# SupplyBox_v3.net
KiCad netlist of a schematic drawn in Altium Designer
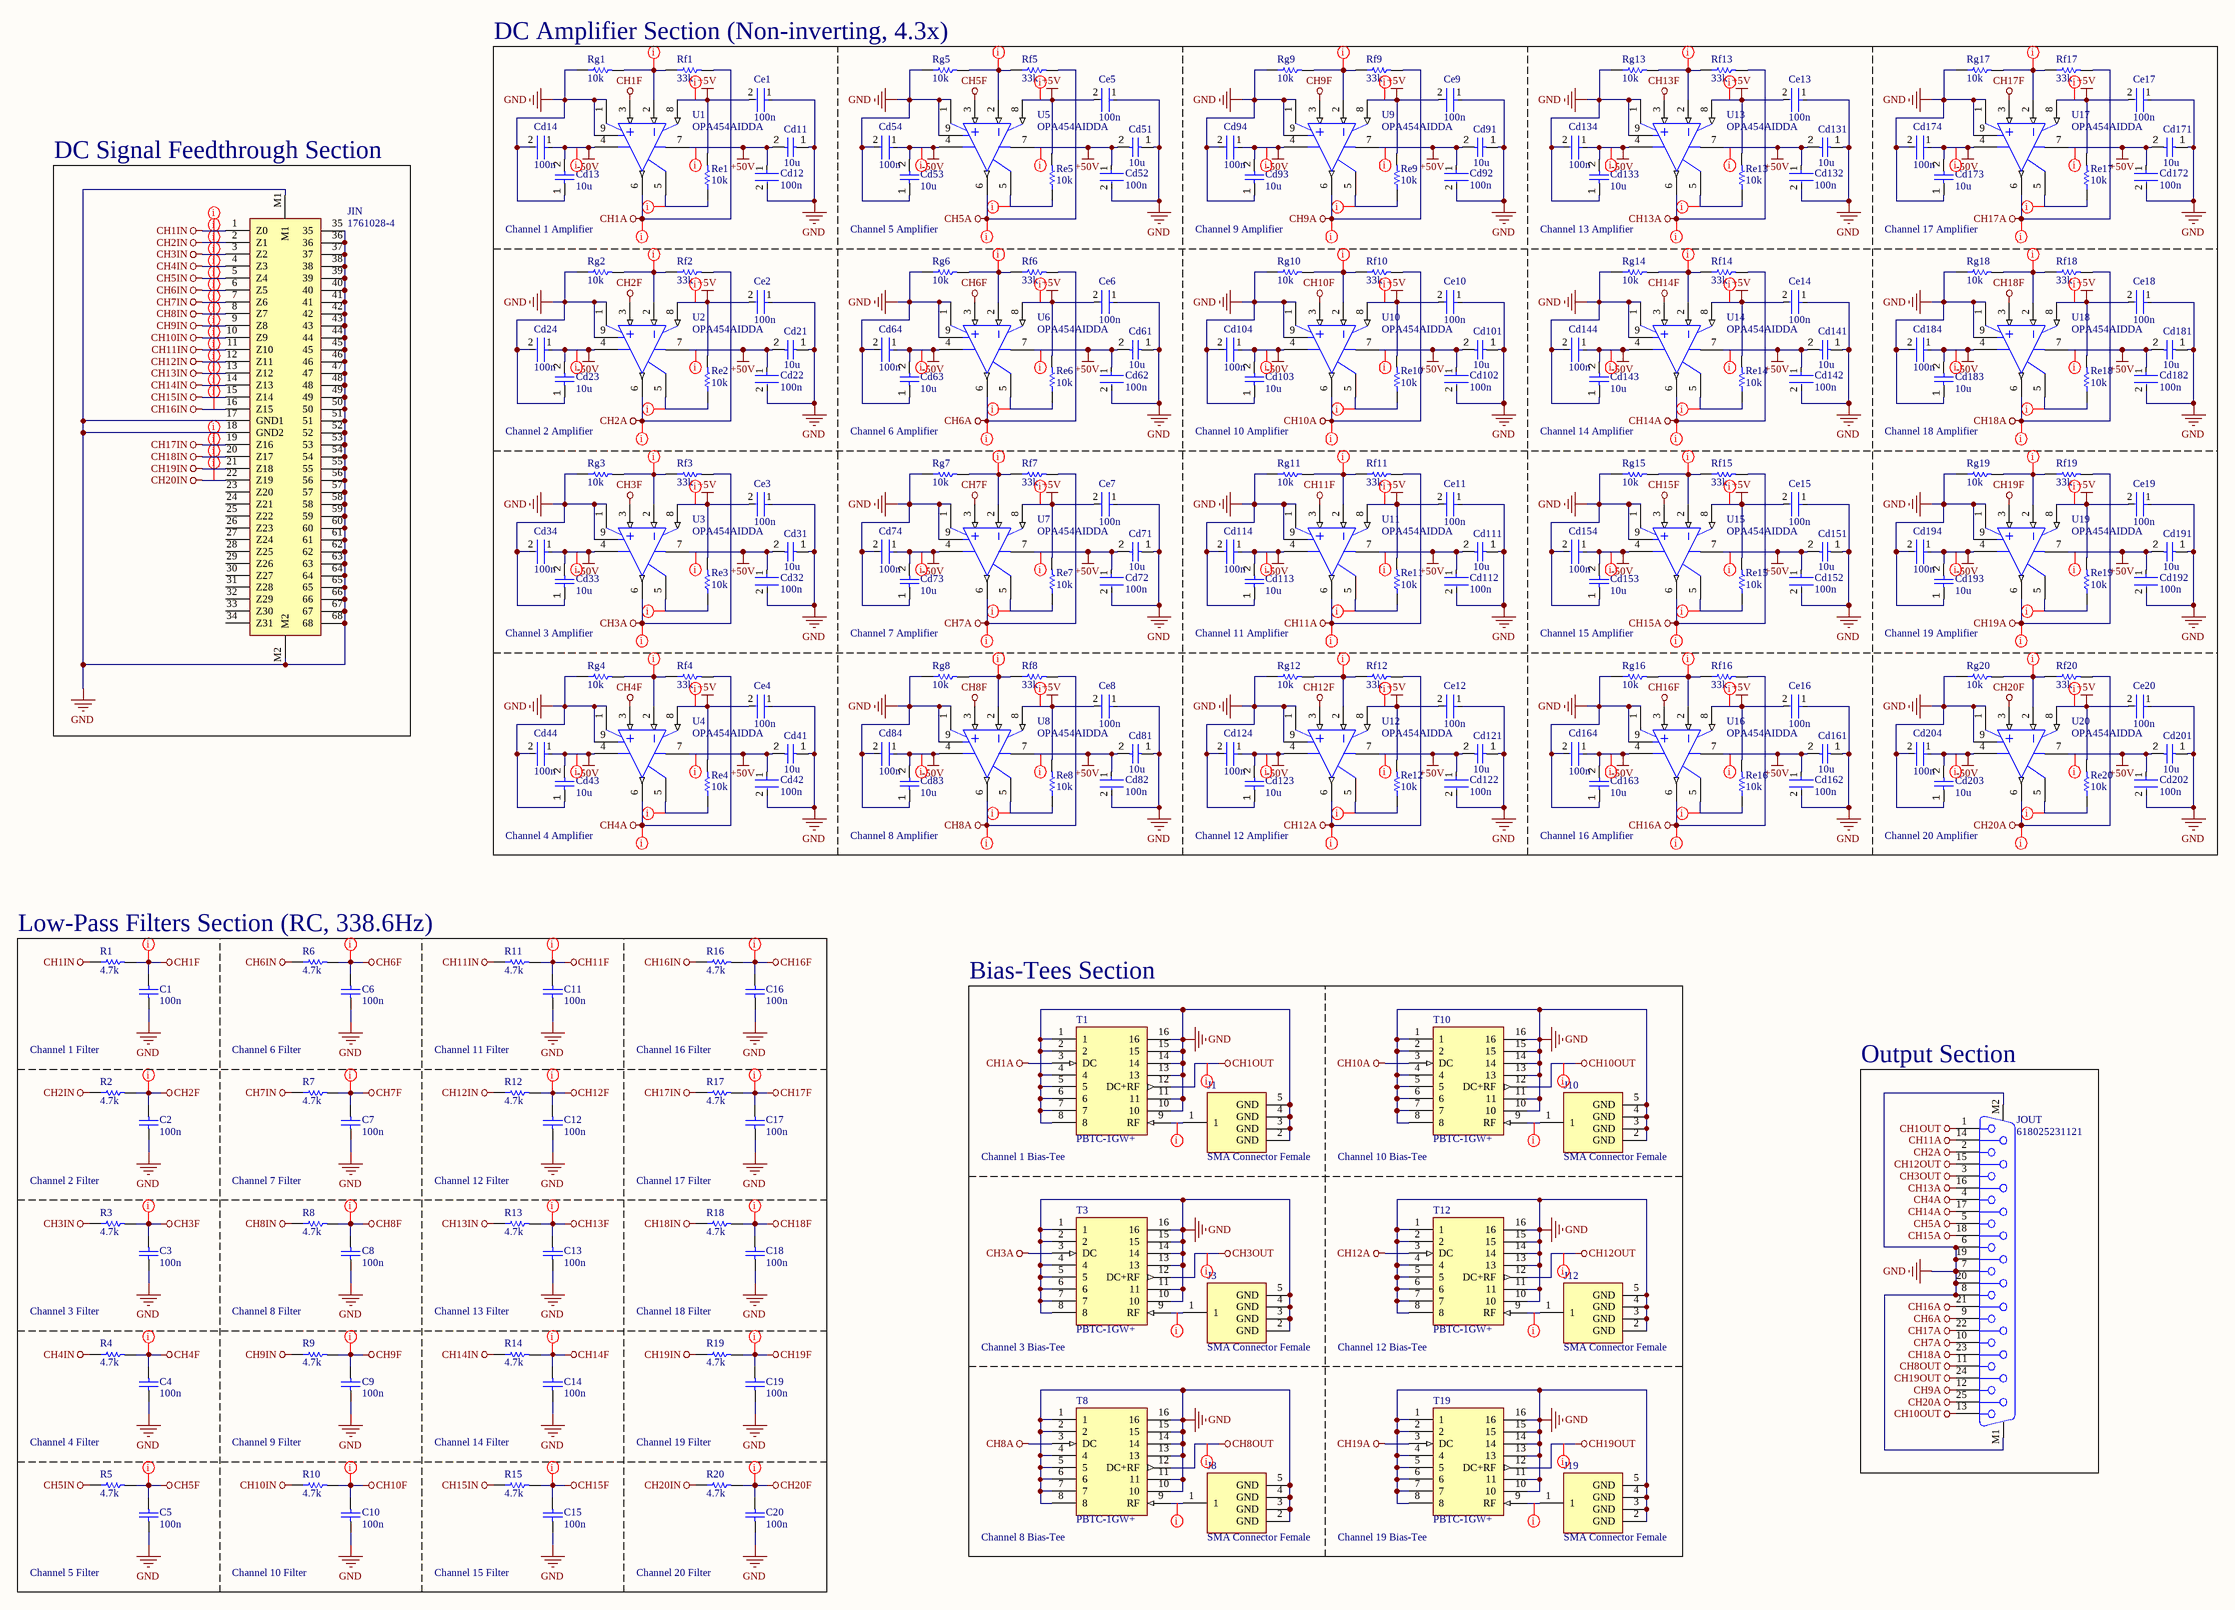
[diagram p0: SupplyBox_v3.SchDoc]

(export (version "E")
  (design (tool "Eeschema 10.0.6"))
  (components
    (comp (ref "C1")
      (value "100n")
      (footprint "CAPC2013X145X48NL20T23")
      (fields (field (name "MANUFACTURER") "Vitramon") (field (name "PART NUMBER") "VJ0805Y104KNAAT"))
      (libsource (lib "Altium Content Vault") (part "CAP"))
    )
    (comp (ref "C2")
      (value "100n")
      (footprint "CAPC2013X145X48NL20T23")
      (fields (field (name "MANUFACTURER") "Vitramon") (field (name "PART NUMBER") "VJ0805Y104KNAAT"))
      (libsource (lib "Altium Content Vault") (part "CAP"))
    )
    (comp (ref "C3")
      (value "100n")
      (footprint "CAPC2013X145X48NL20T23")
      (fields (field (name "MANUFACTURER") "Vitramon") (field (name "PART NUMBER") "VJ0805Y104KNAAT"))
      (libsource (lib "Altium Content Vault") (part "CAP"))
    )
    (comp (ref "C4")
      (value "100n")
      (footprint "CAPC2013X145X48NL20T23")
      (fields (field (name "MANUFACTURER") "Vitramon") (field (name "PART NUMBER") "VJ0805Y104KNAAT"))
      (libsource (lib "Altium Content Vault") (part "CAP"))
    )
    (comp (ref "C5")
      (value "100n")
      (footprint "CAPC2013X145X48NL20T23")
      (fields (field (name "MANUFACTURER") "Vitramon") (field (name "PART NUMBER") "VJ0805Y104KNAAT"))
      (libsource (lib "Altium Content Vault") (part "CAP"))
    )
    (comp (ref "C6")
      (value "100n")
      (footprint "CAPC2013X145X48NL20T23")
      (fields (field (name "MANUFACTURER") "Vitramon") (field (name "PART NUMBER") "VJ0805Y104KNAAT"))
      (libsource (lib "Altium Content Vault") (part "CAP"))
    )
    (comp (ref "C7")
      (value "100n")
      (footprint "CAPC2013X145X48NL20T23")
      (fields (field (name "MANUFACTURER") "Vitramon") (field (name "PART NUMBER") "VJ0805Y104KNAAT"))
      (libsource (lib "Altium Content Vault") (part "CAP"))
    )
    (comp (ref "C8")
      (value "100n")
      (footprint "CAPC2013X145X48NL20T23")
      (fields (field (name "MANUFACTURER") "Vitramon") (field (name "PART NUMBER") "VJ0805Y104KNAAT"))
      (libsource (lib "Altium Content Vault") (part "CAP"))
    )
    (comp (ref "C9")
      (value "100n")
      (footprint "CAPC2013X145X48NL20T23")
      (fields (field (name "MANUFACTURER") "Vitramon") (field (name "PART NUMBER") "VJ0805Y104KNAAT"))
      (libsource (lib "Altium Content Vault") (part "CAP"))
    )
    (comp (ref "C10")
      (value "100n")
      (footprint "CAPC2013X145X48NL20T23")
      (fields (field (name "MANUFACTURER") "Vitramon") (field (name "PART NUMBER") "VJ0805Y104KNAAT"))
      (libsource (lib "Altium Content Vault") (part "CAP"))
    )
    (comp (ref "C11")
      (value "100n")
      (footprint "CAPC2013X145X48NL20T23")
      (fields (field (name "MANUFACTURER") "Vitramon") (field (name "PART NUMBER") "VJ0805Y104KNAAT"))
      (libsource (lib "Altium Content Vault") (part "CAP"))
    )
    (comp (ref "C12")
      (value "100n")
      (footprint "CAPC2013X145X48NL20T23")
      (fields (field (name "MANUFACTURER") "Vitramon") (field (name "PART NUMBER") "VJ0805Y104KNAAT"))
      (libsource (lib "Altium Content Vault") (part "CAP"))
    )
    (comp (ref "C13")
      (value "100n")
      (footprint "CAPC2013X145X48NL20T23")
      (fields (field (name "MANUFACTURER") "Vitramon") (field (name "PART NUMBER") "VJ0805Y104KNAAT"))
      (libsource (lib "Altium Content Vault") (part "CAP"))
    )
    (comp (ref "C14")
      (value "100n")
      (footprint "CAPC2013X145X48NL20T23")
      (fields (field (name "MANUFACTURER") "Vitramon") (field (name "PART NUMBER") "VJ0805Y104KNAAT"))
      (libsource (lib "Altium Content Vault") (part "CAP"))
    )
    (comp (ref "C15")
      (value "100n")
      (footprint "CAPC2013X145X48NL20T23")
      (fields (field (name "MANUFACTURER") "Vitramon") (field (name "PART NUMBER") "VJ0805Y104KNAAT"))
      (libsource (lib "Altium Content Vault") (part "CAP"))
    )
    (comp (ref "C16")
      (value "100n")
      (footprint "CAPC2013X145X48NL20T23")
      (fields (field (name "MANUFACTURER") "Vitramon") (field (name "PART NUMBER") "VJ0805Y104KNAAT"))
      (libsource (lib "Altium Content Vault") (part "CAP"))
    )
    (comp (ref "C17")
      (value "100n")
      (footprint "CAPC2013X145X48NL20T23")
      (fields (field (name "MANUFACTURER") "Vitramon") (field (name "PART NUMBER") "VJ0805Y104KNAAT"))
      (libsource (lib "Altium Content Vault") (part "CAP"))
    )
    (comp (ref "C18")
      (value "100n")
      (footprint "CAPC2013X145X48NL20T23")
      (fields (field (name "MANUFACTURER") "Vitramon") (field (name "PART NUMBER") "VJ0805Y104KNAAT"))
      (libsource (lib "Altium Content Vault") (part "CAP"))
    )
    (comp (ref "C19")
      (value "100n")
      (footprint "CAPC2013X145X48NL20T23")
      (fields (field (name "MANUFACTURER") "Vitramon") (field (name "PART NUMBER") "VJ0805Y104KNAAT"))
      (libsource (lib "Altium Content Vault") (part "CAP"))
    )
    (comp (ref "C20")
      (value "100n")
      (footprint "CAPC2013X145X48NL20T23")
      (fields (field (name "MANUFACTURER") "Vitramon") (field (name "PART NUMBER") "VJ0805Y104KNAAT"))
      (libsource (lib "Altium Content Vault") (part "CAP"))
    )
    (comp (ref "Cd11")
      (value "10u")
      (footprint "RAHV1100M1UCC8002E-Footprint-1")
      (libsource (lib "Li-Ren Liu") (part "CAP-NP-2"))
    )
    (comp (ref "Cd12")
      (value "100n")
      (footprint "FP-CC0805-0_85-MFG")
      (description "CAP CER 0.1UF 25V X7R 0805")
      (fields (field (name "MANUFACTURER PART NUMBER") "CC0805KRX7R8BB104") (field (name "TOLERANCE") "0.1"))
      (libsource (lib "Altium Content Vault") (part "11868f565c42a9108669ba33697ecf6"))
    )
    (comp (ref "Cd13")
      (value "10u")
      (footprint "RAHV1100M1UCC8002E-Footprint-1")
      (libsource (lib "Li-Ren Liu") (part "CAP-NP-2"))
    )
    (comp (ref "Cd14")
      (value "100n")
      (footprint "FP-CC0805-0_85-MFG")
      (description "CAP CER 0.1UF 25V X7R 0805")
      (fields (field (name "MANUFACTURER PART NUMBER") "CC0805KRX7R8BB104") (field (name "TOLERANCE") "0.1"))
      (libsource (lib "Altium Content Vault") (part "11868f565c42a9108669ba33697ecf6"))
    )
    (comp (ref "Cd21")
      (value "10u")
      (footprint "RAHV1100M1UCC8002E-Footprint-1")
      (libsource (lib "Li-Ren Liu") (part "CAP-NP-2"))
    )
    (comp (ref "Cd22")
      (value "100n")
      (footprint "FP-CC0805-0_85-MFG")
      (description "CAP CER 0.1UF 25V X7R 0805")
      (fields (field (name "MANUFACTURER PART NUMBER") "CC0805KRX7R8BB104") (field (name "TOLERANCE") "0.1"))
      (libsource (lib "Altium Content Vault") (part "11868f565c42a9108669ba33697ecf6"))
    )
    (comp (ref "Cd23")
      (value "10u")
      (footprint "RAHV1100M1UCC8002E-Footprint-1")
      (libsource (lib "Li-Ren Liu") (part "CAP-NP-2"))
    )
    (comp (ref "Cd24")
      (value "100n")
      (footprint "FP-CC0805-0_85-MFG")
      (description "CAP CER 0.1UF 25V X7R 0805")
      (fields (field (name "MANUFACTURER PART NUMBER") "CC0805KRX7R8BB104") (field (name "TOLERANCE") "0.1"))
      (libsource (lib "Altium Content Vault") (part "11868f565c42a9108669ba33697ecf6"))
    )
    (comp (ref "Cd31")
      (value "10u")
      (footprint "RAHV1100M1UCC8002E-Footprint-1")
      (libsource (lib "Li-Ren Liu") (part "CAP-NP-2"))
    )
    (comp (ref "Cd32")
      (value "100n")
      (footprint "FP-CC0805-0_85-MFG")
      (description "CAP CER 0.1UF 25V X7R 0805")
      (fields (field (name "MANUFACTURER PART NUMBER") "CC0805KRX7R8BB104") (field (name "TOLERANCE") "0.1"))
      (libsource (lib "Altium Content Vault") (part "11868f565c42a9108669ba33697ecf6"))
    )
    (comp (ref "Cd33")
      (value "10u")
      (footprint "RAHV1100M1UCC8002E-Footprint-1")
      (libsource (lib "Li-Ren Liu") (part "CAP-NP-2"))
    )
    (comp (ref "Cd34")
      (value "100n")
      (footprint "FP-CC0805-0_85-MFG")
      (description "CAP CER 0.1UF 25V X7R 0805")
      (fields (field (name "MANUFACTURER PART NUMBER") "CC0805KRX7R8BB104") (field (name "TOLERANCE") "0.1"))
      (libsource (lib "Altium Content Vault") (part "11868f565c42a9108669ba33697ecf6"))
    )
    (comp (ref "Cd41")
      (value "10u")
      (footprint "RAHV1100M1UCC8002E-Footprint-1")
      (libsource (lib "Li-Ren Liu") (part "CAP-NP-2"))
    )
    (comp (ref "Cd42")
      (value "100n")
      (footprint "FP-CC0805-0_85-MFG")
      (description "CAP CER 0.1UF 25V X7R 0805")
      (fields (field (name "MANUFACTURER PART NUMBER") "CC0805KRX7R8BB104") (field (name "TOLERANCE") "0.1"))
      (libsource (lib "Altium Content Vault") (part "11868f565c42a9108669ba33697ecf6"))
    )
    (comp (ref "Cd43")
      (value "10u")
      (footprint "RAHV1100M1UCC8002E-Footprint-1")
      (libsource (lib "Li-Ren Liu") (part "CAP-NP-2"))
    )
    (comp (ref "Cd44")
      (value "100n")
      (footprint "FP-CC0805-0_85-MFG")
      (description "CAP CER 0.1UF 25V X7R 0805")
      (fields (field (name "MANUFACTURER PART NUMBER") "CC0805KRX7R8BB104") (field (name "TOLERANCE") "0.1"))
      (libsource (lib "Altium Content Vault") (part "11868f565c42a9108669ba33697ecf6"))
    )
    (comp (ref "Cd51")
      (value "10u")
      (footprint "RAHV1100M1UCC8002E-Footprint-1")
      (libsource (lib "Li-Ren Liu") (part "CAP-NP-2"))
    )
    (comp (ref "Cd52")
      (value "100n")
      (footprint "FP-CC0805-0_85-MFG")
      (description "CAP CER 0.1UF 25V X7R 0805")
      (fields (field (name "MANUFACTURER PART NUMBER") "CC0805KRX7R8BB104") (field (name "TOLERANCE") "0.1"))
      (libsource (lib "Altium Content Vault") (part "11868f565c42a9108669ba33697ecf6"))
    )
    (comp (ref "Cd53")
      (value "10u")
      (footprint "RAHV1100M1UCC8002E-Footprint-1")
      (libsource (lib "Li-Ren Liu") (part "CAP-NP-2"))
    )
    (comp (ref "Cd54")
      (value "100n")
      (footprint "FP-CC0805-0_85-MFG")
      (description "CAP CER 0.1UF 25V X7R 0805")
      (fields (field (name "MANUFACTURER PART NUMBER") "CC0805KRX7R8BB104") (field (name "TOLERANCE") "0.1"))
      (libsource (lib "Altium Content Vault") (part "11868f565c42a9108669ba33697ecf6"))
    )
    (comp (ref "Cd61")
      (value "10u")
      (footprint "RAHV1100M1UCC8002E-Footprint-1")
      (libsource (lib "Li-Ren Liu") (part "CAP-NP-2"))
    )
    (comp (ref "Cd62")
      (value "100n")
      (footprint "FP-CC0805-0_85-MFG")
      (description "CAP CER 0.1UF 25V X7R 0805")
      (fields (field (name "MANUFACTURER PART NUMBER") "CC0805KRX7R8BB104") (field (name "TOLERANCE") "0.1"))
      (libsource (lib "Altium Content Vault") (part "11868f565c42a9108669ba33697ecf6"))
    )
    (comp (ref "Cd63")
      (value "10u")
      (footprint "RAHV1100M1UCC8002E-Footprint-1")
      (libsource (lib "Li-Ren Liu") (part "CAP-NP-2"))
    )
    (comp (ref "Cd64")
      (value "100n")
      (footprint "FP-CC0805-0_85-MFG")
      (description "CAP CER 0.1UF 25V X7R 0805")
      (fields (field (name "MANUFACTURER PART NUMBER") "CC0805KRX7R8BB104") (field (name "TOLERANCE") "0.1"))
      (libsource (lib "Altium Content Vault") (part "11868f565c42a9108669ba33697ecf6"))
    )
    (comp (ref "Cd71")
      (value "10u")
      (footprint "RAHV1100M1UCC8002E-Footprint-1")
      (libsource (lib "Li-Ren Liu") (part "CAP-NP-2"))
    )
    (comp (ref "Cd72")
      (value "100n")
      (footprint "FP-CC0805-0_85-MFG")
      (description "CAP CER 0.1UF 25V X7R 0805")
      (fields (field (name "MANUFACTURER PART NUMBER") "CC0805KRX7R8BB104") (field (name "TOLERANCE") "0.1"))
      (libsource (lib "Altium Content Vault") (part "11868f565c42a9108669ba33697ecf6"))
    )
    (comp (ref "Cd73")
      (value "10u")
      (footprint "RAHV1100M1UCC8002E-Footprint-1")
      (libsource (lib "Li-Ren Liu") (part "CAP-NP-2"))
    )
    (comp (ref "Cd74")
      (value "100n")
      (footprint "FP-CC0805-0_85-MFG")
      (description "CAP CER 0.1UF 25V X7R 0805")
      (fields (field (name "MANUFACTURER PART NUMBER") "CC0805KRX7R8BB104") (field (name "TOLERANCE") "0.1"))
      (libsource (lib "Altium Content Vault") (part "11868f565c42a9108669ba33697ecf6"))
    )
    (comp (ref "Cd81")
      (value "10u")
      (footprint "RAHV1100M1UCC8002E-Footprint-1")
      (libsource (lib "Li-Ren Liu") (part "CAP-NP-2"))
    )
    (comp (ref "Cd82")
      (value "100n")
      (footprint "FP-CC0805-0_85-MFG")
      (description "CAP CER 0.1UF 25V X7R 0805")
      (fields (field (name "MANUFACTURER PART NUMBER") "CC0805KRX7R8BB104") (field (name "TOLERANCE") "0.1"))
      (libsource (lib "Altium Content Vault") (part "11868f565c42a9108669ba33697ecf6"))
    )
    (comp (ref "Cd83")
      (value "10u")
      (footprint "RAHV1100M1UCC8002E-Footprint-1")
      (libsource (lib "Li-Ren Liu") (part "CAP-NP-2"))
    )
    (comp (ref "Cd84")
      (value "100n")
      (footprint "FP-CC0805-0_85-MFG")
      (description "CAP CER 0.1UF 25V X7R 0805")
      (fields (field (name "MANUFACTURER PART NUMBER") "CC0805KRX7R8BB104") (field (name "TOLERANCE") "0.1"))
      (libsource (lib "Altium Content Vault") (part "11868f565c42a9108669ba33697ecf6"))
    )
    (comp (ref "Cd91")
      (value "10u")
      (footprint "RAHV1100M1UCC8002E-Footprint-1")
      (libsource (lib "Li-Ren Liu") (part "CAP-NP-2"))
    )
    (comp (ref "Cd92")
      (value "100n")
      (footprint "FP-CC0805-0_85-MFG")
      (description "CAP CER 0.1UF 25V X7R 0805")
      (fields (field (name "MANUFACTURER PART NUMBER") "CC0805KRX7R8BB104") (field (name "TOLERANCE") "0.1"))
      (libsource (lib "Altium Content Vault") (part "11868f565c42a9108669ba33697ecf6"))
    )
    (comp (ref "Cd93")
      (value "10u")
      (footprint "RAHV1100M1UCC8002E-Footprint-1")
      (libsource (lib "Li-Ren Liu") (part "CAP-NP-2"))
    )
    (comp (ref "Cd94")
      (value "100n")
      (footprint "FP-CC0805-0_85-MFG")
      (description "CAP CER 0.1UF 25V X7R 0805")
      (fields (field (name "MANUFACTURER PART NUMBER") "CC0805KRX7R8BB104") (field (name "TOLERANCE") "0.1"))
      (libsource (lib "Altium Content Vault") (part "11868f565c42a9108669ba33697ecf6"))
    )
    (comp (ref "Cd101")
      (value "10u")
      (footprint "RAHV1100M1UCC8002E-Footprint-1")
      (libsource (lib "Li-Ren Liu") (part "CAP-NP-2"))
    )
    (comp (ref "Cd102")
      (value "100n")
      (footprint "FP-CC0805-0_85-MFG")
      (description "CAP CER 0.1UF 25V X7R 0805")
      (fields (field (name "MANUFACTURER PART NUMBER") "CC0805KRX7R8BB104") (field (name "TOLERANCE") "0.1"))
      (libsource (lib "Altium Content Vault") (part "11868f565c42a9108669ba33697ecf6"))
    )
    (comp (ref "Cd103")
      (value "10u")
      (footprint "RAHV1100M1UCC8002E-Footprint-1")
      (libsource (lib "Li-Ren Liu") (part "CAP-NP-2"))
    )
    (comp (ref "Cd104")
      (value "100n")
      (footprint "FP-CC0805-0_85-MFG")
      (description "CAP CER 0.1UF 25V X7R 0805")
      (fields (field (name "MANUFACTURER PART NUMBER") "CC0805KRX7R8BB104") (field (name "TOLERANCE") "0.1"))
      (libsource (lib "Altium Content Vault") (part "11868f565c42a9108669ba33697ecf6"))
    )
    (comp (ref "Cd111")
      (value "10u")
      (footprint "RAHV1100M1UCC8002E-Footprint-1")
      (libsource (lib "Li-Ren Liu") (part "CAP-NP-2"))
    )
    (comp (ref "Cd112")
      (value "100n")
      (footprint "FP-CC0805-0_85-MFG")
      (description "CAP CER 0.1UF 25V X7R 0805")
      (fields (field (name "MANUFACTURER PART NUMBER") "CC0805KRX7R8BB104") (field (name "TOLERANCE") "0.1"))
      (libsource (lib "Altium Content Vault") (part "11868f565c42a9108669ba33697ecf6"))
    )
    (comp (ref "Cd113")
      (value "10u")
      (footprint "RAHV1100M1UCC8002E-Footprint-1")
      (libsource (lib "Li-Ren Liu") (part "CAP-NP-2"))
    )
    (comp (ref "Cd114")
      (value "100n")
      (footprint "FP-CC0805-0_85-MFG")
      (description "CAP CER 0.1UF 25V X7R 0805")
      (fields (field (name "MANUFACTURER PART NUMBER") "CC0805KRX7R8BB104") (field (name "TOLERANCE") "0.1"))
      (libsource (lib "Altium Content Vault") (part "11868f565c42a9108669ba33697ecf6"))
    )
    (comp (ref "Cd121")
      (value "10u")
      (footprint "RAHV1100M1UCC8002E-Footprint-1")
      (libsource (lib "Li-Ren Liu") (part "CAP-NP-2"))
    )
    (comp (ref "Cd122")
      (value "100n")
      (footprint "FP-CC0805-0_85-MFG")
      (description "CAP CER 0.1UF 25V X7R 0805")
      (fields (field (name "MANUFACTURER PART NUMBER") "CC0805KRX7R8BB104") (field (name "TOLERANCE") "0.1"))
      (libsource (lib "Altium Content Vault") (part "11868f565c42a9108669ba33697ecf6"))
    )
    (comp (ref "Cd123")
      (value "10u")
      (footprint "RAHV1100M1UCC8002E-Footprint-1")
      (libsource (lib "Li-Ren Liu") (part "CAP-NP-2"))
    )
    (comp (ref "Cd124")
      (value "100n")
      (footprint "FP-CC0805-0_85-MFG")
      (description "CAP CER 0.1UF 25V X7R 0805")
      (fields (field (name "MANUFACTURER PART NUMBER") "CC0805KRX7R8BB104") (field (name "TOLERANCE") "0.1"))
      (libsource (lib "Altium Content Vault") (part "11868f565c42a9108669ba33697ecf6"))
    )
    (comp (ref "Cd131")
      (value "10u")
      (footprint "RAHV1100M1UCC8002E-Footprint-1")
      (libsource (lib "Li-Ren Liu") (part "CAP-NP-2"))
    )
    (comp (ref "Cd132")
      (value "100n")
      (footprint "FP-CC0805-0_85-MFG")
      (description "CAP CER 0.1UF 25V X7R 0805")
      (fields (field (name "MANUFACTURER PART NUMBER") "CC0805KRX7R8BB104") (field (name "TOLERANCE") "0.1"))
      (libsource (lib "Altium Content Vault") (part "11868f565c42a9108669ba33697ecf6"))
    )
    (comp (ref "Cd133")
      (value "10u")
      (footprint "RAHV1100M1UCC8002E-Footprint-1")
      (libsource (lib "Li-Ren Liu") (part "CAP-NP-2"))
    )
    (comp (ref "Cd134")
      (value "100n")
      (footprint "FP-CC0805-0_85-MFG")
      (description "CAP CER 0.1UF 25V X7R 0805")
      (fields (field (name "MANUFACTURER PART NUMBER") "CC0805KRX7R8BB104") (field (name "TOLERANCE") "0.1"))
      (libsource (lib "Altium Content Vault") (part "11868f565c42a9108669ba33697ecf6"))
    )
    (comp (ref "Cd141")
      (value "10u")
      (footprint "RAHV1100M1UCC8002E-Footprint-1")
      (libsource (lib "Li-Ren Liu") (part "CAP-NP-2"))
    )
    (comp (ref "Cd142")
      (value "100n")
      (footprint "FP-CC0805-0_85-MFG")
      (description "CAP CER 0.1UF 25V X7R 0805")
      (fields (field (name "MANUFACTURER PART NUMBER") "CC0805KRX7R8BB104") (field (name "TOLERANCE") "0.1"))
      (libsource (lib "Altium Content Vault") (part "11868f565c42a9108669ba33697ecf6"))
    )
    (comp (ref "Cd143")
      (value "10u")
      (footprint "RAHV1100M1UCC8002E-Footprint-1")
      (libsource (lib "Li-Ren Liu") (part "CAP-NP-2"))
    )
    (comp (ref "Cd144")
      (value "100n")
      (footprint "FP-CC0805-0_85-MFG")
      (description "CAP CER 0.1UF 25V X7R 0805")
      (fields (field (name "MANUFACTURER PART NUMBER") "CC0805KRX7R8BB104") (field (name "TOLERANCE") "0.1"))
      (libsource (lib "Altium Content Vault") (part "11868f565c42a9108669ba33697ecf6"))
    )
    (comp (ref "Cd151")
      (value "10u")
      (footprint "RAHV1100M1UCC8002E-Footprint-1")
      (libsource (lib "Li-Ren Liu") (part "CAP-NP-2"))
    )
    (comp (ref "Cd152")
      (value "100n")
      (footprint "FP-CC0805-0_85-MFG")
      (description "CAP CER 0.1UF 25V X7R 0805")
      (fields (field (name "MANUFACTURER PART NUMBER") "CC0805KRX7R8BB104") (field (name "TOLERANCE") "0.1"))
      (libsource (lib "Altium Content Vault") (part "11868f565c42a9108669ba33697ecf6"))
    )
    (comp (ref "Cd153")
      (value "10u")
      (footprint "RAHV1100M1UCC8002E-Footprint-1")
      (libsource (lib "Li-Ren Liu") (part "CAP-NP-2"))
    )
    (comp (ref "Cd154")
      (value "100n")
      (footprint "FP-CC0805-0_85-MFG")
      (description "CAP CER 0.1UF 25V X7R 0805")
      (fields (field (name "MANUFACTURER PART NUMBER") "CC0805KRX7R8BB104") (field (name "TOLERANCE") "0.1"))
      (libsource (lib "Altium Content Vault") (part "11868f565c42a9108669ba33697ecf6"))
    )
    (comp (ref "Cd161")
      (value "10u")
      (footprint "RAHV1100M1UCC8002E-Footprint-1")
      (libsource (lib "Li-Ren Liu") (part "CAP-NP-2"))
    )
    (comp (ref "Cd162")
      (value "100n")
      (footprint "FP-CC0805-0_85-MFG")
      (description "CAP CER 0.1UF 25V X7R 0805")
      (fields (field (name "MANUFACTURER PART NUMBER") "CC0805KRX7R8BB104") (field (name "TOLERANCE") "0.1"))
      (libsource (lib "Altium Content Vault") (part "11868f565c42a9108669ba33697ecf6"))
    )
    (comp (ref "Cd163")
      (value "10u")
      (footprint "RAHV1100M1UCC8002E-Footprint-1")
      (libsource (lib "Li-Ren Liu") (part "CAP-NP-2"))
    )
    (comp (ref "Cd164")
      (value "100n")
      (footprint "FP-CC0805-0_85-MFG")
      (description "CAP CER 0.1UF 25V X7R 0805")
      (fields (field (name "MANUFACTURER PART NUMBER") "CC0805KRX7R8BB104") (field (name "TOLERANCE") "0.1"))
      (libsource (lib "Altium Content Vault") (part "11868f565c42a9108669ba33697ecf6"))
    )
    (comp (ref "Cd171")
      (value "10u")
      (footprint "RAHV1100M1UCC8002E-Footprint-1")
      (libsource (lib "Li-Ren Liu") (part "CAP-NP-2"))
    )
    (comp (ref "Cd172")
      (value "100n")
      (footprint "FP-CC0805-0_85-MFG")
      (description "CAP CER 0.1UF 25V X7R 0805")
      (fields (field (name "MANUFACTURER PART NUMBER") "CC0805KRX7R8BB104") (field (name "TOLERANCE") "0.1"))
      (libsource (lib "Altium Content Vault") (part "11868f565c42a9108669ba33697ecf6"))
    )
    (comp (ref "Cd173")
      (value "10u")
      (footprint "RAHV1100M1UCC8002E-Footprint-1")
      (libsource (lib "Li-Ren Liu") (part "CAP-NP-2"))
    )
    (comp (ref "Cd174")
      (value "100n")
      (footprint "FP-CC0805-0_85-MFG")
      (description "CAP CER 0.1UF 25V X7R 0805")
      (fields (field (name "MANUFACTURER PART NUMBER") "CC0805KRX7R8BB104") (field (name "TOLERANCE") "0.1"))
      (libsource (lib "Altium Content Vault") (part "11868f565c42a9108669ba33697ecf6"))
    )
    (comp (ref "Cd181")
      (value "10u")
      (footprint "RAHV1100M1UCC8002E-Footprint-1")
      (libsource (lib "Li-Ren Liu") (part "CAP-NP-2"))
    )
    (comp (ref "Cd182")
      (value "100n")
      (footprint "FP-CC0805-0_85-MFG")
      (description "CAP CER 0.1UF 25V X7R 0805")
      (fields (field (name "MANUFACTURER PART NUMBER") "CC0805KRX7R8BB104") (field (name "TOLERANCE") "0.1"))
      (libsource (lib "Altium Content Vault") (part "11868f565c42a9108669ba33697ecf6"))
    )
    (comp (ref "Cd183")
      (value "10u")
      (footprint "RAHV1100M1UCC8002E-Footprint-1")
      (libsource (lib "Li-Ren Liu") (part "CAP-NP-2"))
    )
    (comp (ref "Cd184")
      (value "100n")
      (footprint "FP-CC0805-0_85-MFG")
      (description "CAP CER 0.1UF 25V X7R 0805")
      (fields (field (name "MANUFACTURER PART NUMBER") "CC0805KRX7R8BB104") (field (name "TOLERANCE") "0.1"))
      (libsource (lib "Altium Content Vault") (part "11868f565c42a9108669ba33697ecf6"))
    )
    (comp (ref "Cd191")
      (value "10u")
      (footprint "RAHV1100M1UCC8002E-Footprint-1")
      (libsource (lib "Li-Ren Liu") (part "CAP-NP-2"))
    )
    (comp (ref "Cd192")
      (value "100n")
      (footprint "FP-CC0805-0_85-MFG")
      (description "CAP CER 0.1UF 25V X7R 0805")
      (fields (field (name "MANUFACTURER PART NUMBER") "CC0805KRX7R8BB104") (field (name "TOLERANCE") "0.1"))
      (libsource (lib "Altium Content Vault") (part "11868f565c42a9108669ba33697ecf6"))
    )
    (comp (ref "Cd193")
      (value "10u")
      (footprint "RAHV1100M1UCC8002E-Footprint-1")
      (libsource (lib "Li-Ren Liu") (part "CAP-NP-2"))
    )
    (comp (ref "Cd194")
      (value "100n")
      (footprint "FP-CC0805-0_85-MFG")
      (description "CAP CER 0.1UF 25V X7R 0805")
      (fields (field (name "MANUFACTURER PART NUMBER") "CC0805KRX7R8BB104") (field (name "TOLERANCE") "0.1"))
      (libsource (lib "Altium Content Vault") (part "11868f565c42a9108669ba33697ecf6"))
    )
    (comp (ref "Cd201")
      (value "10u")
      (footprint "RAHV1100M1UCC8002E-Footprint-1")
      (libsource (lib "Li-Ren Liu") (part "CAP-NP-2"))
    )
    (comp (ref "Cd202")
      (value "100n")
      (footprint "FP-CC0805-0_85-MFG")
      (description "CAP CER 0.1UF 25V X7R 0805")
      (fields (field (name "MANUFACTURER PART NUMBER") "CC0805KRX7R8BB104") (field (name "TOLERANCE") "0.1"))
      (libsource (lib "Altium Content Vault") (part "11868f565c42a9108669ba33697ecf6"))
    )
    (comp (ref "Cd203")
      (value "10u")
      (footprint "RAHV1100M1UCC8002E-Footprint-1")
      (libsource (lib "Li-Ren Liu") (part "CAP-NP-2"))
    )
    (comp (ref "Cd204")
      (value "100n")
      (footprint "FP-CC0805-0_85-MFG")
      (description "CAP CER 0.1UF 25V X7R 0805")
      (fields (field (name "MANUFACTURER PART NUMBER") "CC0805KRX7R8BB104") (field (name "TOLERANCE") "0.1"))
      (libsource (lib "Altium Content Vault") (part "11868f565c42a9108669ba33697ecf6"))
    )
    (comp (ref "Ce1")
      (value "100n")
      (footprint "FP-CC0805-0_85-MFG")
      (description "CAP CER 0.1UF 25V X7R 0805")
      (fields (field (name "MANUFACTURER PART NUMBER") "CC0805KRX7R8BB104") (field (name "TOLERANCE") "0.1"))
      (libsource (lib "Altium Content Vault") (part "11868f565c42a9108669ba33697ecf6"))
    )
    (comp (ref "Ce2")
      (value "100n")
      (footprint "FP-CC0805-0_85-MFG")
      (description "CAP CER 0.1UF 25V X7R 0805")
      (fields (field (name "MANUFACTURER PART NUMBER") "CC0805KRX7R8BB104") (field (name "TOLERANCE") "0.1"))
      (libsource (lib "Altium Content Vault") (part "11868f565c42a9108669ba33697ecf6"))
    )
    (comp (ref "Ce3")
      (value "100n")
      (footprint "FP-CC0805-0_85-MFG")
      (description "CAP CER 0.1UF 25V X7R 0805")
      (fields (field (name "MANUFACTURER PART NUMBER") "CC0805KRX7R8BB104") (field (name "TOLERANCE") "0.1"))
      (libsource (lib "Altium Content Vault") (part "11868f565c42a9108669ba33697ecf6"))
    )
    (comp (ref "Ce4")
      (value "100n")
      (footprint "FP-CC0805-0_85-MFG")
      (description "CAP CER 0.1UF 25V X7R 0805")
      (fields (field (name "MANUFACTURER PART NUMBER") "CC0805KRX7R8BB104") (field (name "TOLERANCE") "0.1"))
      (libsource (lib "Altium Content Vault") (part "11868f565c42a9108669ba33697ecf6"))
    )
    (comp (ref "Ce5")
      (value "100n")
      (footprint "FP-CC0805-0_85-MFG")
      (description "CAP CER 0.1UF 25V X7R 0805")
      (fields (field (name "MANUFACTURER PART NUMBER") "CC0805KRX7R8BB104") (field (name "TOLERANCE") "0.1"))
      (libsource (lib "Altium Content Vault") (part "11868f565c42a9108669ba33697ecf6"))
    )
    (comp (ref "Ce6")
      (value "100n")
      (footprint "FP-CC0805-0_85-MFG")
      (description "CAP CER 0.1UF 25V X7R 0805")
      (fields (field (name "MANUFACTURER PART NUMBER") "CC0805KRX7R8BB104") (field (name "TOLERANCE") "0.1"))
      (libsource (lib "Altium Content Vault") (part "11868f565c42a9108669ba33697ecf6"))
    )
    (comp (ref "Ce7")
      (value "100n")
      (footprint "FP-CC0805-0_85-MFG")
      (description "CAP CER 0.1UF 25V X7R 0805")
      (fields (field (name "MANUFACTURER PART NUMBER") "CC0805KRX7R8BB104") (field (name "TOLERANCE") "0.1"))
      (libsource (lib "Altium Content Vault") (part "11868f565c42a9108669ba33697ecf6"))
    )
    (comp (ref "Ce8")
      (value "100n")
      (footprint "FP-CC0805-0_85-MFG")
      (description "CAP CER 0.1UF 25V X7R 0805")
      (fields (field (name "MANUFACTURER PART NUMBER") "CC0805KRX7R8BB104") (field (name "TOLERANCE") "0.1"))
      (libsource (lib "Altium Content Vault") (part "11868f565c42a9108669ba33697ecf6"))
    )
    (comp (ref "Ce9")
      (value "100n")
      (footprint "FP-CC0805-0_85-MFG")
      (description "CAP CER 0.1UF 25V X7R 0805")
      (fields (field (name "MANUFACTURER PART NUMBER") "CC0805KRX7R8BB104") (field (name "TOLERANCE") "0.1"))
      (libsource (lib "Altium Content Vault") (part "11868f565c42a9108669ba33697ecf6"))
    )
    (comp (ref "Ce10")
      (value "100n")
      (footprint "FP-CC0805-0_85-MFG")
      (description "CAP CER 0.1UF 25V X7R 0805")
      (fields (field (name "MANUFACTURER PART NUMBER") "CC0805KRX7R8BB104") (field (name "TOLERANCE") "0.1"))
      (libsource (lib "Altium Content Vault") (part "11868f565c42a9108669ba33697ecf6"))
    )
    (comp (ref "Ce11")
      (value "100n")
      (footprint "FP-CC0805-0_85-MFG")
      (description "CAP CER 0.1UF 25V X7R 0805")
      (fields (field (name "MANUFACTURER PART NUMBER") "CC0805KRX7R8BB104") (field (name "TOLERANCE") "0.1"))
      (libsource (lib "Altium Content Vault") (part "11868f565c42a9108669ba33697ecf6"))
    )
    (comp (ref "Ce12")
      (value "100n")
      (footprint "FP-CC0805-0_85-MFG")
      (description "CAP CER 0.1UF 25V X7R 0805")
      (fields (field (name "MANUFACTURER PART NUMBER") "CC0805KRX7R8BB104") (field (name "TOLERANCE") "0.1"))
      (libsource (lib "Altium Content Vault") (part "11868f565c42a9108669ba33697ecf6"))
    )
    (comp (ref "Ce13")
      (value "100n")
      (footprint "FP-CC0805-0_85-MFG")
      (description "CAP CER 0.1UF 25V X7R 0805")
      (fields (field (name "MANUFACTURER PART NUMBER") "CC0805KRX7R8BB104") (field (name "TOLERANCE") "0.1"))
      (libsource (lib "Altium Content Vault") (part "11868f565c42a9108669ba33697ecf6"))
    )
    (comp (ref "Ce14")
      (value "100n")
      (footprint "FP-CC0805-0_85-MFG")
      (description "CAP CER 0.1UF 25V X7R 0805")
      (fields (field (name "MANUFACTURER PART NUMBER") "CC0805KRX7R8BB104") (field (name "TOLERANCE") "0.1"))
      (libsource (lib "Altium Content Vault") (part "11868f565c42a9108669ba33697ecf6"))
    )
    (comp (ref "Ce15")
      (value "100n")
      (footprint "FP-CC0805-0_85-MFG")
      (description "CAP CER 0.1UF 25V X7R 0805")
      (fields (field (name "MANUFACTURER PART NUMBER") "CC0805KRX7R8BB104") (field (name "TOLERANCE") "0.1"))
      (libsource (lib "Altium Content Vault") (part "11868f565c42a9108669ba33697ecf6"))
    )
    (comp (ref "Ce16")
      (value "100n")
      (footprint "FP-CC0805-0_85-MFG")
      (description "CAP CER 0.1UF 25V X7R 0805")
      (fields (field (name "MANUFACTURER PART NUMBER") "CC0805KRX7R8BB104") (field (name "TOLERANCE") "0.1"))
      (libsource (lib "Altium Content Vault") (part "11868f565c42a9108669ba33697ecf6"))
    )
    (comp (ref "Ce17")
      (value "100n")
      (footprint "FP-CC0805-0_85-MFG")
      (description "CAP CER 0.1UF 25V X7R 0805")
      (fields (field (name "MANUFACTURER PART NUMBER") "CC0805KRX7R8BB104") (field (name "TOLERANCE") "0.1"))
      (libsource (lib "Altium Content Vault") (part "11868f565c42a9108669ba33697ecf6"))
    )
    (comp (ref "Ce18")
      (value "100n")
      (footprint "FP-CC0805-0_85-MFG")
      (description "CAP CER 0.1UF 25V X7R 0805")
      (fields (field (name "MANUFACTURER PART NUMBER") "CC0805KRX7R8BB104") (field (name "TOLERANCE") "0.1"))
      (libsource (lib "Altium Content Vault") (part "11868f565c42a9108669ba33697ecf6"))
    )
    (comp (ref "Ce19")
      (value "100n")
      (footprint "FP-CC0805-0_85-MFG")
      (description "CAP CER 0.1UF 25V X7R 0805")
      (fields (field (name "MANUFACTURER PART NUMBER") "CC0805KRX7R8BB104") (field (name "TOLERANCE") "0.1"))
      (libsource (lib "Altium Content Vault") (part "11868f565c42a9108669ba33697ecf6"))
    )
    (comp (ref "Ce20")
      (value "100n")
      (footprint "FP-CC0805-0_85-MFG")
      (description "CAP CER 0.1UF 25V X7R 0805")
      (fields (field (name "MANUFACTURER PART NUMBER") "CC0805KRX7R8BB104") (field (name "TOLERANCE") "0.1"))
      (libsource (lib "Altium Content Vault") (part "11868f565c42a9108669ba33697ecf6"))
    )
    (comp (ref "J1")
      (value "SMA Connector Female")
      (footprint "SMA_Smaller")
      (description "Our smaller SMA Female Connector purchased from amazon.com")
      (libsource (lib "Li-Ren Liu") (part "SMA-CONN"))
    )
    (comp (ref "J3")
      (value "SMA Connector Female")
      (footprint "SMA_Smaller")
      (description "Our smaller SMA Female Connector purchased from amazon.com")
      (libsource (lib "Li-Ren Liu") (part "SMA-CONN"))
    )
    (comp (ref "J8")
      (value "SMA Connector Female")
      (footprint "SMA_Smaller")
      (description "Our smaller SMA Female Connector purchased from amazon.com")
      (libsource (lib "Li-Ren Liu") (part "SMA-CONN"))
    )
    (comp (ref "J10")
      (value "SMA Connector Female")
      (footprint "SMA_Smaller")
      (description "Our smaller SMA Female Connector purchased from amazon.com")
      (libsource (lib "Li-Ren Liu") (part "SMA-CONN"))
    )
    (comp (ref "J12")
      (value "SMA Connector Female")
      (footprint "SMA_Smaller")
      (description "Our smaller SMA Female Connector purchased from amazon.com")
      (libsource (lib "Li-Ren Liu") (part "SMA-CONN"))
    )
    (comp (ref "J19")
      (value "SMA Connector Female")
      (footprint "SMA_Smaller")
      (description "Our smaller SMA Female Connector purchased from amazon.com")
      (libsource (lib "Li-Ren Liu") (part "SMA-CONN"))
    )
    (comp (ref "JIN")
      (value "1761028-4")
      (footprint "1761028-4-Footprint-1")
      (libsource (lib "Li-Ren Liu") (part "1761028-4-Symbol-1"))
    )
    (comp (ref "JOUT")
      (value "618025231121")
      (footprint "618025231121")
      (libsource (lib "Altium Content Vault") (part "D-Sub_Female_25p"))
    )
    (comp (ref "R1")
      (value "4.7k")
      (footprint "RESC2013X60X35NL10T20")
      (description "Chip Resistor, 47 KOhm, +/- 1%, 0.125 W, -55 to 155 degC, 0805 (2012 Metric), RoHS, Tape and Reel")
      (fields (field (name "MANUFACTURER") "Yageo"))
      (libsource (lib "Altium Content Vault") (part "RES-2"))
    )
    (comp (ref "R2")
      (value "4.7k")
      (footprint "RESC2013X60X35NL10T20")
      (description "Chip Resistor, 47 KOhm, +/- 1%, 0.125 W, -55 to 155 degC, 0805 (2012 Metric), RoHS, Tape and Reel")
      (fields (field (name "MANUFACTURER") "Yageo"))
      (libsource (lib "Altium Content Vault") (part "RES-2"))
    )
    (comp (ref "R3")
      (value "4.7k")
      (footprint "RESC2013X60X35NL10T20")
      (description "Chip Resistor, 47 KOhm, +/- 1%, 0.125 W, -55 to 155 degC, 0805 (2012 Metric), RoHS, Tape and Reel")
      (fields (field (name "MANUFACTURER") "Yageo"))
      (libsource (lib "Altium Content Vault") (part "RES-2"))
    )
    (comp (ref "R4")
      (value "4.7k")
      (footprint "RESC2013X60X35NL10T20")
      (description "Chip Resistor, 47 KOhm, +/- 1%, 0.125 W, -55 to 155 degC, 0805 (2012 Metric), RoHS, Tape and Reel")
      (fields (field (name "MANUFACTURER") "Yageo"))
      (libsource (lib "Altium Content Vault") (part "RES-2"))
    )
    (comp (ref "R5")
      (value "4.7k")
      (footprint "RESC2013X60X35NL10T20")
      (description "Chip Resistor, 47 KOhm, +/- 1%, 0.125 W, -55 to 155 degC, 0805 (2012 Metric), RoHS, Tape and Reel")
      (fields (field (name "MANUFACTURER") "Yageo"))
      (libsource (lib "Altium Content Vault") (part "RES-2"))
    )
    (comp (ref "R6")
      (value "4.7k")
      (footprint "RESC2013X60X35NL10T20")
      (description "Chip Resistor, 47 KOhm, +/- 1%, 0.125 W, -55 to 155 degC, 0805 (2012 Metric), RoHS, Tape and Reel")
      (fields (field (name "MANUFACTURER") "Yageo"))
      (libsource (lib "Altium Content Vault") (part "RES-2"))
    )
    (comp (ref "R7")
      (value "4.7k")
      (footprint "RESC2013X60X35NL10T20")
      (description "Chip Resistor, 47 KOhm, +/- 1%, 0.125 W, -55 to 155 degC, 0805 (2012 Metric), RoHS, Tape and Reel")
      (fields (field (name "MANUFACTURER") "Yageo"))
      (libsource (lib "Altium Content Vault") (part "RES-2"))
    )
    (comp (ref "R8")
      (value "4.7k")
      (footprint "RESC2013X60X35NL10T20")
      (description "Chip Resistor, 47 KOhm, +/- 1%, 0.125 W, -55 to 155 degC, 0805 (2012 Metric), RoHS, Tape and Reel")
      (fields (field (name "MANUFACTURER") "Yageo"))
      (libsource (lib "Altium Content Vault") (part "RES-2"))
    )
    (comp (ref "R9")
      (value "4.7k")
      (footprint "RESC2013X60X35NL10T20")
      (description "Chip Resistor, 47 KOhm, +/- 1%, 0.125 W, -55 to 155 degC, 0805 (2012 Metric), RoHS, Tape and Reel")
      (fields (field (name "MANUFACTURER") "Yageo"))
      (libsource (lib "Altium Content Vault") (part "RES-2"))
    )
    (comp (ref "R10")
      (value "4.7k")
      (footprint "RESC2013X60X35NL10T20")
      (description "Chip Resistor, 47 KOhm, +/- 1%, 0.125 W, -55 to 155 degC, 0805 (2012 Metric), RoHS, Tape and Reel")
      (fields (field (name "MANUFACTURER") "Yageo"))
      (libsource (lib "Altium Content Vault") (part "RES-2"))
    )
    (comp (ref "R11")
      (value "4.7k")
      (footprint "RESC2013X60X35NL10T20")
      (description "Chip Resistor, 47 KOhm, +/- 1%, 0.125 W, -55 to 155 degC, 0805 (2012 Metric), RoHS, Tape and Reel")
      (fields (field (name "MANUFACTURER") "Yageo"))
      (libsource (lib "Altium Content Vault") (part "RES-2"))
    )
    (comp (ref "R12")
      (value "4.7k")
      (footprint "RESC2013X60X35NL10T20")
      (description "Chip Resistor, 47 KOhm, +/- 1%, 0.125 W, -55 to 155 degC, 0805 (2012 Metric), RoHS, Tape and Reel")
      (fields (field (name "MANUFACTURER") "Yageo"))
      (libsource (lib "Altium Content Vault") (part "RES-2"))
    )
    (comp (ref "R13")
      (value "4.7k")
      (footprint "RESC2013X60X35NL10T20")
      (description "Chip Resistor, 47 KOhm, +/- 1%, 0.125 W, -55 to 155 degC, 0805 (2012 Metric), RoHS, Tape and Reel")
      (fields (field (name "MANUFACTURER") "Yageo"))
      (libsource (lib "Altium Content Vault") (part "RES-2"))
    )
    (comp (ref "R14")
      (value "4.7k")
      (footprint "RESC2013X60X35NL10T20")
      (description "Chip Resistor, 47 KOhm, +/- 1%, 0.125 W, -55 to 155 degC, 0805 (2012 Metric), RoHS, Tape and Reel")
      (fields (field (name "MANUFACTURER") "Yageo"))
      (libsource (lib "Altium Content Vault") (part "RES-2"))
    )
    (comp (ref "R15")
      (value "4.7k")
      (footprint "RESC2013X60X35NL10T20")
      (description "Chip Resistor, 47 KOhm, +/- 1%, 0.125 W, -55 to 155 degC, 0805 (2012 Metric), RoHS, Tape and Reel")
      (fields (field (name "MANUFACTURER") "Yageo"))
      (libsource (lib "Altium Content Vault") (part "RES-2"))
    )
    (comp (ref "R16")
      (value "4.7k")
      (footprint "RESC2013X60X35NL10T20")
      (description "Chip Resistor, 47 KOhm, +/- 1%, 0.125 W, -55 to 155 degC, 0805 (2012 Metric), RoHS, Tape and Reel")
      (fields (field (name "MANUFACTURER") "Yageo"))
      (libsource (lib "Altium Content Vault") (part "RES-2"))
    )
    (comp (ref "R17")
      (value "4.7k")
      (footprint "RESC2013X60X35NL10T20")
      (description "Chip Resistor, 47 KOhm, +/- 1%, 0.125 W, -55 to 155 degC, 0805 (2012 Metric), RoHS, Tape and Reel")
      (fields (field (name "MANUFACTURER") "Yageo"))
      (libsource (lib "Altium Content Vault") (part "RES-2"))
    )
    (comp (ref "R18")
      (value "4.7k")
      (footprint "RESC2013X60X35NL10T20")
      (description "Chip Resistor, 47 KOhm, +/- 1%, 0.125 W, -55 to 155 degC, 0805 (2012 Metric), RoHS, Tape and Reel")
      (fields (field (name "MANUFACTURER") "Yageo"))
      (libsource (lib "Altium Content Vault") (part "RES-2"))
    )
    (comp (ref "R19")
      (value "4.7k")
      (footprint "RESC2013X60X35NL10T20")
      (description "Chip Resistor, 47 KOhm, +/- 1%, 0.125 W, -55 to 155 degC, 0805 (2012 Metric), RoHS, Tape and Reel")
      (fields (field (name "MANUFACTURER") "Yageo"))
      (libsource (lib "Altium Content Vault") (part "RES-2"))
    )
    (comp (ref "R20")
      (value "4.7k")
      (footprint "RESC2013X60X35NL10T20")
      (description "Chip Resistor, 47 KOhm, +/- 1%, 0.125 W, -55 to 155 degC, 0805 (2012 Metric), RoHS, Tape and Reel")
      (fields (field (name "MANUFACTURER") "Yageo"))
      (libsource (lib "Altium Content Vault") (part "RES-2"))
    )
    (comp (ref "Re1")
      (value "10k")
      (footprint "RESC2013X60X35ML10T20")
      (description "Chip Resistor, 1 KOhm, +/- 1%, 125 mW, -55 to 155 degC, 0805 (2012 Metric), RoHS, Tape and Reel")
      (fields (field (name "TOLERANCE") "1%") (field (name "MANUFACTURER") "Yageo"))
      (libsource (lib "Altium Content Vault") (part "RES-2"))
    )
    (comp (ref "Re2")
      (value "10k")
      (footprint "RESC2013X60X35ML10T20")
      (description "Chip Resistor, 1 KOhm, +/- 1%, 125 mW, -55 to 155 degC, 0805 (2012 Metric), RoHS, Tape and Reel")
      (fields (field (name "TOLERANCE") "1%") (field (name "MANUFACTURER") "Yageo"))
      (libsource (lib "Altium Content Vault") (part "RES-2"))
    )
    (comp (ref "Re3")
      (value "10k")
      (footprint "RESC2013X60X35ML10T20")
      (description "Chip Resistor, 1 KOhm, +/- 1%, 125 mW, -55 to 155 degC, 0805 (2012 Metric), RoHS, Tape and Reel")
      (fields (field (name "TOLERANCE") "1%") (field (name "MANUFACTURER") "Yageo"))
      (libsource (lib "Altium Content Vault") (part "RES-2"))
    )
    (comp (ref "Re4")
      (value "10k")
      (footprint "RESC2013X60X35ML10T20")
      (description "Chip Resistor, 1 KOhm, +/- 1%, 125 mW, -55 to 155 degC, 0805 (2012 Metric), RoHS, Tape and Reel")
      (fields (field (name "TOLERANCE") "1%") (field (name "MANUFACTURER") "Yageo"))
      (libsource (lib "Altium Content Vault") (part "RES-2"))
    )
    (comp (ref "Re5")
      (value "10k")
      (footprint "RESC2013X60X35ML10T20")
      (description "Chip Resistor, 1 KOhm, +/- 1%, 125 mW, -55 to 155 degC, 0805 (2012 Metric), RoHS, Tape and Reel")
      (fields (field (name "TOLERANCE") "1%") (field (name "MANUFACTURER") "Yageo"))
      (libsource (lib "Altium Content Vault") (part "RES-2"))
    )
    (comp (ref "Re6")
      (value "10k")
      (footprint "RESC2013X60X35ML10T20")
      (description "Chip Resistor, 1 KOhm, +/- 1%, 125 mW, -55 to 155 degC, 0805 (2012 Metric), RoHS, Tape and Reel")
      (fields (field (name "TOLERANCE") "1%") (field (name "MANUFACTURER") "Yageo"))
      (libsource (lib "Altium Content Vault") (part "RES-2"))
    )
    (comp (ref "Re7")
      (value "10k")
      (footprint "RESC2013X60X35ML10T20")
      (description "Chip Resistor, 1 KOhm, +/- 1%, 125 mW, -55 to 155 degC, 0805 (2012 Metric), RoHS, Tape and Reel")
      (fields (field (name "TOLERANCE") "1%") (field (name "MANUFACTURER") "Yageo"))
      (libsource (lib "Altium Content Vault") (part "RES-2"))
    )
    (comp (ref "Re8")
      (value "10k")
      (footprint "RESC2013X60X35ML10T20")
      (description "Chip Resistor, 1 KOhm, +/- 1%, 125 mW, -55 to 155 degC, 0805 (2012 Metric), RoHS, Tape and Reel")
      (fields (field (name "TOLERANCE") "1%") (field (name "MANUFACTURER") "Yageo"))
      (libsource (lib "Altium Content Vault") (part "RES-2"))
    )
    (comp (ref "Re9")
      (value "10k")
      (footprint "RESC2013X60X35ML10T20")
      (description "Chip Resistor, 1 KOhm, +/- 1%, 125 mW, -55 to 155 degC, 0805 (2012 Metric), RoHS, Tape and Reel")
      (fields (field (name "TOLERANCE") "1%") (field (name "MANUFACTURER") "Yageo"))
      (libsource (lib "Altium Content Vault") (part "RES-2"))
    )
    (comp (ref "Re10")
      (value "10k")
      (footprint "RESC2013X60X35ML10T20")
      (description "Chip Resistor, 1 KOhm, +/- 1%, 125 mW, -55 to 155 degC, 0805 (2012 Metric), RoHS, Tape and Reel")
      (fields (field (name "TOLERANCE") "1%") (field (name "MANUFACTURER") "Yageo"))
      (libsource (lib "Altium Content Vault") (part "RES-2"))
    )
    (comp (ref "Re11")
      (value "10k")
      (footprint "RESC2013X60X35ML10T20")
      (description "Chip Resistor, 1 KOhm, +/- 1%, 125 mW, -55 to 155 degC, 0805 (2012 Metric), RoHS, Tape and Reel")
      (fields (field (name "TOLERANCE") "1%") (field (name "MANUFACTURER") "Yageo"))
      (libsource (lib "Altium Content Vault") (part "RES-2"))
    )
    (comp (ref "Re12")
      (value "10k")
      (footprint "RESC2013X60X35ML10T20")
      (description "Chip Resistor, 1 KOhm, +/- 1%, 125 mW, -55 to 155 degC, 0805 (2012 Metric), RoHS, Tape and Reel")
      (fields (field (name "TOLERANCE") "1%") (field (name "MANUFACTURER") "Yageo"))
      (libsource (lib "Altium Content Vault") (part "RES-2"))
    )
    (comp (ref "Re13")
      (value "10k")
      (footprint "RESC2013X60X35ML10T20")
      (description "Chip Resistor, 1 KOhm, +/- 1%, 125 mW, -55 to 155 degC, 0805 (2012 Metric), RoHS, Tape and Reel")
      (fields (field (name "TOLERANCE") "1%") (field (name "MANUFACTURER") "Yageo"))
      (libsource (lib "Altium Content Vault") (part "RES-2"))
    )
    (comp (ref "Re14")
      (value "10k")
      (footprint "RESC2013X60X35ML10T20")
      (description "Chip Resistor, 1 KOhm, +/- 1%, 125 mW, -55 to 155 degC, 0805 (2012 Metric), RoHS, Tape and Reel")
      (fields (field (name "TOLERANCE") "1%") (field (name "MANUFACTURER") "Yageo"))
      (libsource (lib "Altium Content Vault") (part "RES-2"))
    )
    (comp (ref "Re15")
      (value "10k")
      (footprint "RESC2013X60X35ML10T20")
      (description "Chip Resistor, 1 KOhm, +/- 1%, 125 mW, -55 to 155 degC, 0805 (2012 Metric), RoHS, Tape and Reel")
      (fields (field (name "TOLERANCE") "1%") (field (name "MANUFACTURER") "Yageo"))
      (libsource (lib "Altium Content Vault") (part "RES-2"))
    )
    (comp (ref "Re16")
      (value "10k")
      (footprint "RESC2013X60X35ML10T20")
      (description "Chip Resistor, 1 KOhm, +/- 1%, 125 mW, -55 to 155 degC, 0805 (2012 Metric), RoHS, Tape and Reel")
      (fields (field (name "TOLERANCE") "1%") (field (name "MANUFACTURER") "Yageo"))
      (libsource (lib "Altium Content Vault") (part "RES-2"))
    )
    (comp (ref "Re17")
      (value "10k")
      (footprint "RESC2013X60X35ML10T20")
      (description "Chip Resistor, 1 KOhm, +/- 1%, 125 mW, -55 to 155 degC, 0805 (2012 Metric), RoHS, Tape and Reel")
      (fields (field (name "TOLERANCE") "1%") (field (name "MANUFACTURER") "Yageo"))
      (libsource (lib "Altium Content Vault") (part "RES-2"))
    )
    (comp (ref "Re18")
      (value "10k")
      (footprint "RESC2013X60X35ML10T20")
      (description "Chip Resistor, 1 KOhm, +/- 1%, 125 mW, -55 to 155 degC, 0805 (2012 Metric), RoHS, Tape and Reel")
      (fields (field (name "TOLERANCE") "1%") (field (name "MANUFACTURER") "Yageo"))
      (libsource (lib "Altium Content Vault") (part "RES-2"))
    )
    (comp (ref "Re19")
      (value "10k")
      (footprint "RESC2013X60X35ML10T20")
      (description "Chip Resistor, 1 KOhm, +/- 1%, 125 mW, -55 to 155 degC, 0805 (2012 Metric), RoHS, Tape and Reel")
      (fields (field (name "TOLERANCE") "1%") (field (name "MANUFACTURER") "Yageo"))
      (libsource (lib "Altium Content Vault") (part "RES-2"))
    )
    (comp (ref "Re20")
      (value "10k")
      (footprint "RESC2013X60X35ML10T20")
      (description "Chip Resistor, 1 KOhm, +/- 1%, 125 mW, -55 to 155 degC, 0805 (2012 Metric), RoHS, Tape and Reel")
      (fields (field (name "TOLERANCE") "1%") (field (name "MANUFACTURER") "Yageo"))
      (libsource (lib "Altium Content Vault") (part "RES-2"))
    )
    (comp (ref "Rf1")
      (value "33k")
      (footprint "RESC2013X60X35ML10T20")
      (description "Chip Resistor, 3.3 KOhm, +/- 1%, 0.125 W, -55 to 155 degC, 0805 (2012 Metric), RoHS, Tape and Reel")
      (fields (field (name "TOLERANCE") "1%") (field (name "MANUFACTURER") "Yageo"))
      (libsource (lib "Altium Content Vault") (part "RES-2"))
    )
    (comp (ref "Rf2")
      (value "33k")
      (footprint "RESC2013X60X35ML10T20")
      (description "Chip Resistor, 3.3 KOhm, +/- 1%, 0.125 W, -55 to 155 degC, 0805 (2012 Metric), RoHS, Tape and Reel")
      (fields (field (name "TOLERANCE") "1%") (field (name "MANUFACTURER") "Yageo"))
      (libsource (lib "Altium Content Vault") (part "RES-2"))
    )
    (comp (ref "Rf3")
      (value "33k")
      (footprint "RESC2013X60X35ML10T20")
      (description "Chip Resistor, 3.3 KOhm, +/- 1%, 0.125 W, -55 to 155 degC, 0805 (2012 Metric), RoHS, Tape and Reel")
      (fields (field (name "TOLERANCE") "1%") (field (name "MANUFACTURER") "Yageo"))
      (libsource (lib "Altium Content Vault") (part "RES-2"))
    )
    (comp (ref "Rf4")
      (value "33k")
      (footprint "RESC2013X60X35ML10T20")
      (description "Chip Resistor, 3.3 KOhm, +/- 1%, 0.125 W, -55 to 155 degC, 0805 (2012 Metric), RoHS, Tape and Reel")
      (fields (field (name "TOLERANCE") "1%") (field (name "MANUFACTURER") "Yageo"))
      (libsource (lib "Altium Content Vault") (part "RES-2"))
    )
    (comp (ref "Rf5")
      (value "33k")
      (footprint "RESC2013X60X35ML10T20")
      (description "Chip Resistor, 3.3 KOhm, +/- 1%, 0.125 W, -55 to 155 degC, 0805 (2012 Metric), RoHS, Tape and Reel")
      (fields (field (name "TOLERANCE") "1%") (field (name "MANUFACTURER") "Yageo"))
      (libsource (lib "Altium Content Vault") (part "RES-2"))
    )
    (comp (ref "Rf6")
      (value "33k")
      (footprint "RESC2013X60X35ML10T20")
      (description "Chip Resistor, 3.3 KOhm, +/- 1%, 0.125 W, -55 to 155 degC, 0805 (2012 Metric), RoHS, Tape and Reel")
      (fields (field (name "TOLERANCE") "1%") (field (name "MANUFACTURER") "Yageo"))
      (libsource (lib "Altium Content Vault") (part "RES-2"))
    )
    (comp (ref "Rf7")
      (value "33k")
      (footprint "RESC2013X60X35ML10T20")
      (description "Chip Resistor, 3.3 KOhm, +/- 1%, 0.125 W, -55 to 155 degC, 0805 (2012 Metric), RoHS, Tape and Reel")
      (fields (field (name "TOLERANCE") "1%") (field (name "MANUFACTURER") "Yageo"))
      (libsource (lib "Altium Content Vault") (part "RES-2"))
    )
    (comp (ref "Rf8")
      (value "33k")
      (footprint "RESC2013X60X35ML10T20")
      (description "Chip Resistor, 3.3 KOhm, +/- 1%, 0.125 W, -55 to 155 degC, 0805 (2012 Metric), RoHS, Tape and Reel")
      (fields (field (name "TOLERANCE") "1%") (field (name "MANUFACTURER") "Yageo"))
      (libsource (lib "Altium Content Vault") (part "RES-2"))
    )
    (comp (ref "Rf9")
      (value "33k")
      (footprint "RESC2013X60X35ML10T20")
      (description "Chip Resistor, 3.3 KOhm, +/- 1%, 0.125 W, -55 to 155 degC, 0805 (2012 Metric), RoHS, Tape and Reel")
      (fields (field (name "TOLERANCE") "1%") (field (name "MANUFACTURER") "Yageo"))
      (libsource (lib "Altium Content Vault") (part "RES-2"))
    )
    (comp (ref "Rf10")
      (value "33k")
      (footprint "RESC2013X60X35ML10T20")
      (description "Chip Resistor, 3.3 KOhm, +/- 1%, 0.125 W, -55 to 155 degC, 0805 (2012 Metric), RoHS, Tape and Reel")
      (fields (field (name "TOLERANCE") "1%") (field (name "MANUFACTURER") "Yageo"))
      (libsource (lib "Altium Content Vault") (part "RES-2"))
    )
    (comp (ref "Rf11")
      (value "33k")
      (footprint "RESC2013X60X35ML10T20")
      (description "Chip Resistor, 3.3 KOhm, +/- 1%, 0.125 W, -55 to 155 degC, 0805 (2012 Metric), RoHS, Tape and Reel")
      (fields (field (name "TOLERANCE") "1%") (field (name "MANUFACTURER") "Yageo"))
      (libsource (lib "Altium Content Vault") (part "RES-2"))
    )
    (comp (ref "Rf12")
      (value "33k")
      (footprint "RESC2013X60X35ML10T20")
      (description "Chip Resistor, 3.3 KOhm, +/- 1%, 0.125 W, -55 to 155 degC, 0805 (2012 Metric), RoHS, Tape and Reel")
      (fields (field (name "TOLERANCE") "1%") (field (name "MANUFACTURER") "Yageo"))
      (libsource (lib "Altium Content Vault") (part "RES-2"))
    )
    (comp (ref "Rf13")
      (value "33k")
      (footprint "RESC2013X60X35ML10T20")
      (description "Chip Resistor, 3.3 KOhm, +/- 1%, 0.125 W, -55 to 155 degC, 0805 (2012 Metric), RoHS, Tape and Reel")
      (fields (field (name "TOLERANCE") "1%") (field (name "MANUFACTURER") "Yageo"))
      (libsource (lib "Altium Content Vault") (part "RES-2"))
    )
    (comp (ref "Rf14")
      (value "33k")
      (footprint "RESC2013X60X35ML10T20")
      (description "Chip Resistor, 3.3 KOhm, +/- 1%, 0.125 W, -55 to 155 degC, 0805 (2012 Metric), RoHS, Tape and Reel")
      (fields (field (name "TOLERANCE") "1%") (field (name "MANUFACTURER") "Yageo"))
      (libsource (lib "Altium Content Vault") (part "RES-2"))
    )
    (comp (ref "Rf15")
      (value "33k")
      (footprint "RESC2013X60X35ML10T20")
      (description "Chip Resistor, 3.3 KOhm, +/- 1%, 0.125 W, -55 to 155 degC, 0805 (2012 Metric), RoHS, Tape and Reel")
      (fields (field (name "TOLERANCE") "1%") (field (name "MANUFACTURER") "Yageo"))
      (libsource (lib "Altium Content Vault") (part "RES-2"))
    )
    (comp (ref "Rf16")
      (value "33k")
      (footprint "RESC2013X60X35ML10T20")
      (description "Chip Resistor, 3.3 KOhm, +/- 1%, 0.125 W, -55 to 155 degC, 0805 (2012 Metric), RoHS, Tape and Reel")
      (fields (field (name "TOLERANCE") "1%") (field (name "MANUFACTURER") "Yageo"))
      (libsource (lib "Altium Content Vault") (part "RES-2"))
    )
    (comp (ref "Rf17")
      (value "33k")
      (footprint "RESC2013X60X35ML10T20")
      (description "Chip Resistor, 3.3 KOhm, +/- 1%, 0.125 W, -55 to 155 degC, 0805 (2012 Metric), RoHS, Tape and Reel")
      (fields (field (name "TOLERANCE") "1%") (field (name "MANUFACTURER") "Yageo"))
      (libsource (lib "Altium Content Vault") (part "RES-2"))
    )
    (comp (ref "Rf18")
      (value "33k")
      (footprint "RESC2013X60X35ML10T20")
      (description "Chip Resistor, 3.3 KOhm, +/- 1%, 0.125 W, -55 to 155 degC, 0805 (2012 Metric), RoHS, Tape and Reel")
      (fields (field (name "TOLERANCE") "1%") (field (name "MANUFACTURER") "Yageo"))
      (libsource (lib "Altium Content Vault") (part "RES-2"))
    )
    (comp (ref "Rf19")
      (value "33k")
      (footprint "RESC2013X60X35ML10T20")
      (description "Chip Resistor, 3.3 KOhm, +/- 1%, 0.125 W, -55 to 155 degC, 0805 (2012 Metric), RoHS, Tape and Reel")
      (fields (field (name "TOLERANCE") "1%") (field (name "MANUFACTURER") "Yageo"))
      (libsource (lib "Altium Content Vault") (part "RES-2"))
    )
    (comp (ref "Rf20")
      (value "33k")
      (footprint "RESC2013X60X35ML10T20")
      (description "Chip Resistor, 3.3 KOhm, +/- 1%, 0.125 W, -55 to 155 degC, 0805 (2012 Metric), RoHS, Tape and Reel")
      (fields (field (name "TOLERANCE") "1%") (field (name "MANUFACTURER") "Yageo"))
      (libsource (lib "Altium Content Vault") (part "RES-2"))
    )
    (comp (ref "Rg1")
      (value "10k")
      (footprint "RESC2013X60X35ML10T20")
      (description "Chip Resistor, 1 KOhm, +/- 1%, 125 mW, -55 to 155 degC, 0805 (2012 Metric), RoHS, Tape and Reel")
      (fields (field (name "TOLERANCE") "1%") (field (name "MANUFACTURER") "Yageo"))
      (libsource (lib "Altium Content Vault") (part "RES-2"))
    )
    (comp (ref "Rg2")
      (value "10k")
      (footprint "RESC2013X60X35ML10T20")
      (description "Chip Resistor, 1 KOhm, +/- 1%, 125 mW, -55 to 155 degC, 0805 (2012 Metric), RoHS, Tape and Reel")
      (fields (field (name "TOLERANCE") "1%") (field (name "MANUFACTURER") "Yageo"))
      (libsource (lib "Altium Content Vault") (part "RES-2"))
    )
    (comp (ref "Rg3")
      (value "10k")
      (footprint "RESC2013X60X35ML10T20")
      (description "Chip Resistor, 1 KOhm, +/- 1%, 125 mW, -55 to 155 degC, 0805 (2012 Metric), RoHS, Tape and Reel")
      (fields (field (name "TOLERANCE") "1%") (field (name "MANUFACTURER") "Yageo"))
      (libsource (lib "Altium Content Vault") (part "RES-2"))
    )
    (comp (ref "Rg4")
      (value "10k")
      (footprint "RESC2013X60X35ML10T20")
      (description "Chip Resistor, 1 KOhm, +/- 1%, 125 mW, -55 to 155 degC, 0805 (2012 Metric), RoHS, Tape and Reel")
      (fields (field (name "TOLERANCE") "1%") (field (name "MANUFACTURER") "Yageo"))
      (libsource (lib "Altium Content Vault") (part "RES-2"))
    )
    (comp (ref "Rg5")
      (value "10k")
      (footprint "RESC2013X60X35ML10T20")
      (description "Chip Resistor, 1 KOhm, +/- 1%, 125 mW, -55 to 155 degC, 0805 (2012 Metric), RoHS, Tape and Reel")
      (fields (field (name "TOLERANCE") "1%") (field (name "MANUFACTURER") "Yageo"))
      (libsource (lib "Altium Content Vault") (part "RES-2"))
    )
    (comp (ref "Rg6")
      (value "10k")
      (footprint "RESC2013X60X35ML10T20")
      (description "Chip Resistor, 1 KOhm, +/- 1%, 125 mW, -55 to 155 degC, 0805 (2012 Metric), RoHS, Tape and Reel")
      (fields (field (name "TOLERANCE") "1%") (field (name "MANUFACTURER") "Yageo"))
      (libsource (lib "Altium Content Vault") (part "RES-2"))
    )
    (comp (ref "Rg7")
      (value "10k")
      (footprint "RESC2013X60X35ML10T20")
      (description "Chip Resistor, 1 KOhm, +/- 1%, 125 mW, -55 to 155 degC, 0805 (2012 Metric), RoHS, Tape and Reel")
      (fields (field (name "TOLERANCE") "1%") (field (name "MANUFACTURER") "Yageo"))
      (libsource (lib "Altium Content Vault") (part "RES-2"))
    )
    (comp (ref "Rg8")
      (value "10k")
      (footprint "RESC2013X60X35ML10T20")
      (description "Chip Resistor, 1 KOhm, +/- 1%, 125 mW, -55 to 155 degC, 0805 (2012 Metric), RoHS, Tape and Reel")
      (fields (field (name "TOLERANCE") "1%") (field (name "MANUFACTURER") "Yageo"))
      (libsource (lib "Altium Content Vault") (part "RES-2"))
    )
    (comp (ref "Rg9")
      (value "10k")
      (footprint "RESC2013X60X35ML10T20")
      (description "Chip Resistor, 1 KOhm, +/- 1%, 125 mW, -55 to 155 degC, 0805 (2012 Metric), RoHS, Tape and Reel")
      (fields (field (name "TOLERANCE") "1%") (field (name "MANUFACTURER") "Yageo"))
      (libsource (lib "Altium Content Vault") (part "RES-2"))
    )
    (comp (ref "Rg10")
      (value "10k")
      (footprint "RESC2013X60X35ML10T20")
      (description "Chip Resistor, 1 KOhm, +/- 1%, 125 mW, -55 to 155 degC, 0805 (2012 Metric), RoHS, Tape and Reel")
      (fields (field (name "TOLERANCE") "1%") (field (name "MANUFACTURER") "Yageo"))
      (libsource (lib "Altium Content Vault") (part "RES-2"))
    )
    (comp (ref "Rg11")
      (value "10k")
      (footprint "RESC2013X60X35ML10T20")
      (description "Chip Resistor, 1 KOhm, +/- 1%, 125 mW, -55 to 155 degC, 0805 (2012 Metric), RoHS, Tape and Reel")
      (fields (field (name "TOLERANCE") "1%") (field (name "MANUFACTURER") "Yageo"))
      (libsource (lib "Altium Content Vault") (part "RES-2"))
    )
    (comp (ref "Rg12")
      (value "10k")
      (footprint "RESC2013X60X35ML10T20")
      (description "Chip Resistor, 1 KOhm, +/- 1%, 125 mW, -55 to 155 degC, 0805 (2012 Metric), RoHS, Tape and Reel")
      (fields (field (name "TOLERANCE") "1%") (field (name "MANUFACTURER") "Yageo"))
      (libsource (lib "Altium Content Vault") (part "RES-2"))
    )
    (comp (ref "Rg13")
      (value "10k")
      (footprint "RESC2013X60X35ML10T20")
      (description "Chip Resistor, 1 KOhm, +/- 1%, 125 mW, -55 to 155 degC, 0805 (2012 Metric), RoHS, Tape and Reel")
      (fields (field (name "TOLERANCE") "1%") (field (name "MANUFACTURER") "Yageo"))
      (libsource (lib "Altium Content Vault") (part "RES-2"))
    )
    (comp (ref "Rg14")
      (value "10k")
      (footprint "RESC2013X60X35ML10T20")
      (description "Chip Resistor, 1 KOhm, +/- 1%, 125 mW, -55 to 155 degC, 0805 (2012 Metric), RoHS, Tape and Reel")
      (fields (field (name "TOLERANCE") "1%") (field (name "MANUFACTURER") "Yageo"))
      (libsource (lib "Altium Content Vault") (part "RES-2"))
    )
    (comp (ref "Rg15")
      (value "10k")
      (footprint "RESC2013X60X35ML10T20")
      (description "Chip Resistor, 1 KOhm, +/- 1%, 125 mW, -55 to 155 degC, 0805 (2012 Metric), RoHS, Tape and Reel")
      (fields (field (name "TOLERANCE") "1%") (field (name "MANUFACTURER") "Yageo"))
      (libsource (lib "Altium Content Vault") (part "RES-2"))
    )
    (comp (ref "Rg16")
      (value "10k")
      (footprint "RESC2013X60X35ML10T20")
      (description "Chip Resistor, 1 KOhm, +/- 1%, 125 mW, -55 to 155 degC, 0805 (2012 Metric), RoHS, Tape and Reel")
      (fields (field (name "TOLERANCE") "1%") (field (name "MANUFACTURER") "Yageo"))
      (libsource (lib "Altium Content Vault") (part "RES-2"))
    )
    (comp (ref "Rg17")
      (value "10k")
      (footprint "RESC2013X60X35ML10T20")
      (description "Chip Resistor, 1 KOhm, +/- 1%, 125 mW, -55 to 155 degC, 0805 (2012 Metric), RoHS, Tape and Reel")
      (fields (field (name "TOLERANCE") "1%") (field (name "MANUFACTURER") "Yageo"))
      (libsource (lib "Altium Content Vault") (part "RES-2"))
    )
    (comp (ref "Rg18")
      (value "10k")
      (footprint "RESC2013X60X35ML10T20")
      (description "Chip Resistor, 1 KOhm, +/- 1%, 125 mW, -55 to 155 degC, 0805 (2012 Metric), RoHS, Tape and Reel")
      (fields (field (name "TOLERANCE") "1%") (field (name "MANUFACTURER") "Yageo"))
      (libsource (lib "Altium Content Vault") (part "RES-2"))
    )
    (comp (ref "Rg19")
      (value "10k")
      (footprint "RESC2013X60X35ML10T20")
      (description "Chip Resistor, 1 KOhm, +/- 1%, 125 mW, -55 to 155 degC, 0805 (2012 Metric), RoHS, Tape and Reel")
      (fields (field (name "TOLERANCE") "1%") (field (name "MANUFACTURER") "Yageo"))
      (libsource (lib "Altium Content Vault") (part "RES-2"))
    )
    (comp (ref "Rg20")
      (value "10k")
      (footprint "RESC2013X60X35ML10T20")
      (description "Chip Resistor, 1 KOhm, +/- 1%, 125 mW, -55 to 155 degC, 0805 (2012 Metric), RoHS, Tape and Reel")
      (fields (field (name "TOLERANCE") "1%") (field (name "MANUFACTURER") "Yageo"))
      (libsource (lib "Altium Content Vault") (part "RES-2"))
    )
    (comp (ref "T1")
      (value "PBTC-1GW+")
      (footprint "PBTC-1GW+")
      (description "Mini-Circuit Bias-Tee (Version 2)")
      (libsource (lib "Li-Ren Liu") (part "PBTC-1GW+"))
    )
    (comp (ref "T3")
      (value "PBTC-1GW+")
      (footprint "PBTC-1GW+")
      (description "Mini-Circuit Bias-Tee (Version 2)")
      (libsource (lib "Li-Ren Liu") (part "PBTC-1GW+"))
    )
    (comp (ref "T8")
      (value "PBTC-1GW+")
      (footprint "PBTC-1GW+")
      (description "Mini-Circuit Bias-Tee (Version 2)")
      (libsource (lib "Li-Ren Liu") (part "PBTC-1GW+"))
    )
    (comp (ref "T10")
      (value "PBTC-1GW+")
      (footprint "PBTC-1GW+")
      (description "Mini-Circuit Bias-Tee (Version 2)")
      (libsource (lib "Li-Ren Liu") (part "PBTC-1GW+"))
    )
    (comp (ref "T12")
      (value "PBTC-1GW+")
      (footprint "PBTC-1GW+")
      (description "Mini-Circuit Bias-Tee (Version 2)")
      (libsource (lib "Li-Ren Liu") (part "PBTC-1GW+"))
    )
    (comp (ref "T19")
      (value "PBTC-1GW+")
      (footprint "PBTC-1GW+")
      (description "Mini-Circuit Bias-Tee (Version 2)")
      (libsource (lib "Li-Ren Liu") (part "PBTC-1GW+"))
    )
    (comp (ref "U1")
      (value "OPA454AIDDA")
      (footprint "DDA0008C_L")
      (fields (field (name "MANUFACTURER") "Texas Instruments"))
      (libsource (lib "Altium Content Vault") (part "TI-OPA454-DDA8"))
    )
    (comp (ref "U2")
      (value "OPA454AIDDA")
      (footprint "DDA0008C_L")
      (fields (field (name "MANUFACTURER") "Texas Instruments"))
      (libsource (lib "Altium Content Vault") (part "TI-OPA454-DDA8"))
    )
    (comp (ref "U3")
      (value "OPA454AIDDA")
      (footprint "DDA0008C_L")
      (fields (field (name "MANUFACTURER") "Texas Instruments"))
      (libsource (lib "Altium Content Vault") (part "TI-OPA454-DDA8"))
    )
    (comp (ref "U4")
      (value "OPA454AIDDA")
      (footprint "DDA0008C_L")
      (fields (field (name "MANUFACTURER") "Texas Instruments"))
      (libsource (lib "Altium Content Vault") (part "TI-OPA454-DDA8"))
    )
    (comp (ref "U5")
      (value "OPA454AIDDA")
      (footprint "DDA0008C_L")
      (fields (field (name "MANUFACTURER") "Texas Instruments"))
      (libsource (lib "Altium Content Vault") (part "TI-OPA454-DDA8"))
    )
    (comp (ref "U6")
      (value "OPA454AIDDA")
      (footprint "DDA0008C_L")
      (fields (field (name "MANUFACTURER") "Texas Instruments"))
      (libsource (lib "Altium Content Vault") (part "TI-OPA454-DDA8"))
    )
    (comp (ref "U7")
      (value "OPA454AIDDA")
      (footprint "DDA0008C_L")
      (fields (field (name "MANUFACTURER") "Texas Instruments"))
      (libsource (lib "Altium Content Vault") (part "TI-OPA454-DDA8"))
    )
    (comp (ref "U8")
      (value "OPA454AIDDA")
      (footprint "DDA0008C_L")
      (fields (field (name "MANUFACTURER") "Texas Instruments"))
      (libsource (lib "Altium Content Vault") (part "TI-OPA454-DDA8"))
    )
    (comp (ref "U9")
      (value "OPA454AIDDA")
      (footprint "DDA0008C_L")
      (fields (field (name "MANUFACTURER") "Texas Instruments"))
      (libsource (lib "Altium Content Vault") (part "TI-OPA454-DDA8"))
    )
    (comp (ref "U10")
      (value "OPA454AIDDA")
      (footprint "DDA0008C_L")
      (fields (field (name "MANUFACTURER") "Texas Instruments"))
      (libsource (lib "Altium Content Vault") (part "TI-OPA454-DDA8"))
    )
    (comp (ref "U11")
      (value "OPA454AIDDA")
      (footprint "DDA0008C_L")
      (fields (field (name "MANUFACTURER") "Texas Instruments"))
      (libsource (lib "Altium Content Vault") (part "TI-OPA454-DDA8"))
    )
    (comp (ref "U12")
      (value "OPA454AIDDA")
      (footprint "DDA0008C_L")
      (fields (field (name "MANUFACTURER") "Texas Instruments"))
      (libsource (lib "Altium Content Vault") (part "TI-OPA454-DDA8"))
    )
    (comp (ref "U13")
      (value "OPA454AIDDA")
      (footprint "DDA0008C_L")
      (fields (field (name "MANUFACTURER") "Texas Instruments"))
      (libsource (lib "Altium Content Vault") (part "TI-OPA454-DDA8"))
    )
    (comp (ref "U14")
      (value "OPA454AIDDA")
      (footprint "DDA0008C_L")
      (fields (field (name "MANUFACTURER") "Texas Instruments"))
      (libsource (lib "Altium Content Vault") (part "TI-OPA454-DDA8"))
    )
    (comp (ref "U15")
      (value "OPA454AIDDA")
      (footprint "DDA0008C_L")
      (fields (field (name "MANUFACTURER") "Texas Instruments"))
      (libsource (lib "Altium Content Vault") (part "TI-OPA454-DDA8"))
    )
    (comp (ref "U16")
      (value "OPA454AIDDA")
      (footprint "DDA0008C_L")
      (fields (field (name "MANUFACTURER") "Texas Instruments"))
      (libsource (lib "Altium Content Vault") (part "TI-OPA454-DDA8"))
    )
    (comp (ref "U17")
      (value "OPA454AIDDA")
      (footprint "DDA0008C_L")
      (fields (field (name "MANUFACTURER") "Texas Instruments"))
      (libsource (lib "Altium Content Vault") (part "TI-OPA454-DDA8"))
    )
    (comp (ref "U18")
      (value "OPA454AIDDA")
      (footprint "DDA0008C_L")
      (fields (field (name "MANUFACTURER") "Texas Instruments"))
      (libsource (lib "Altium Content Vault") (part "TI-OPA454-DDA8"))
    )
    (comp (ref "U19")
      (value "OPA454AIDDA")
      (footprint "DDA0008C_L")
      (fields (field (name "MANUFACTURER") "Texas Instruments"))
      (libsource (lib "Altium Content Vault") (part "TI-OPA454-DDA8"))
    )
    (comp (ref "U20")
      (value "OPA454AIDDA")
      (footprint "DDA0008C_L")
      (fields (field (name "MANUFACTURER") "Texas Instruments"))
      (libsource (lib "Altium Content Vault") (part "TI-OPA454-DDA8"))
    )
  )
  (nets
    (net (code "1") (name "+5V") (class "Default")
      (node (ref "Ce1") (pin "2") (pinfunction "2_2") (pintype "passive"))
      (node (ref "Ce10") (pin "2") (pinfunction "2_2") (pintype "passive"))
      (node (ref "Ce11") (pin "2") (pinfunction "2_2") (pintype "passive"))
      (node (ref "Ce12") (pin "2") (pinfunction "2_2") (pintype "passive"))
      (node (ref "Ce13") (pin "2") (pinfunction "2_2") (pintype "passive"))
      (node (ref "Ce14") (pin "2") (pinfunction "2_2") (pintype "passive"))
      (node (ref "Ce15") (pin "2") (pinfunction "2_2") (pintype "passive"))
      (node (ref "Ce16") (pin "2") (pinfunction "2_2") (pintype "passive"))
      (node (ref "Ce17") (pin "2") (pinfunction "2_2") (pintype "passive"))
      (node (ref "Ce18") (pin "2") (pinfunction "2_2") (pintype "passive"))
      (node (ref "Ce19") (pin "2") (pinfunction "2_2") (pintype "passive"))
      (node (ref "Ce2") (pin "2") (pinfunction "2_2") (pintype "passive"))
      (node (ref "Ce20") (pin "2") (pinfunction "2_2") (pintype "passive"))
      (node (ref "Ce3") (pin "2") (pinfunction "2_2") (pintype "passive"))
      (node (ref "Ce4") (pin "2") (pinfunction "2_2") (pintype "passive"))
      (node (ref "Ce5") (pin "2") (pinfunction "2_2") (pintype "passive"))
      (node (ref "Ce6") (pin "2") (pinfunction "2_2") (pintype "passive"))
      (node (ref "Ce7") (pin "2") (pinfunction "2_2") (pintype "passive"))
      (node (ref "Ce8") (pin "2") (pinfunction "2_2") (pintype "passive"))
      (node (ref "Ce9") (pin "2") (pinfunction "2_2") (pintype "passive"))
      (node (ref "Re1") (pin "2") (pinfunction "2_2") (pintype "passive"))
      (node (ref "Re10") (pin "2") (pinfunction "2_2") (pintype "passive"))
      (node (ref "Re11") (pin "2") (pinfunction "2_2") (pintype "passive"))
      (node (ref "Re12") (pin "2") (pinfunction "2_2") (pintype "passive"))
      (node (ref "Re13") (pin "2") (pinfunction "2_2") (pintype "passive"))
      (node (ref "Re14") (pin "2") (pinfunction "2_2") (pintype "passive"))
      (node (ref "Re15") (pin "2") (pinfunction "2_2") (pintype "passive"))
      (node (ref "Re16") (pin "2") (pinfunction "2_2") (pintype "passive"))
      (node (ref "Re17") (pin "2") (pinfunction "2_2") (pintype "passive"))
      (node (ref "Re18") (pin "2") (pinfunction "2_2") (pintype "passive"))
      (node (ref "Re19") (pin "2") (pinfunction "2_2") (pintype "passive"))
      (node (ref "Re2") (pin "2") (pinfunction "2_2") (pintype "passive"))
      (node (ref "Re20") (pin "2") (pinfunction "2_2") (pintype "passive"))
      (node (ref "Re3") (pin "2") (pinfunction "2_2") (pintype "passive"))
      (node (ref "Re4") (pin "2") (pinfunction "2_2") (pintype "passive"))
      (node (ref "Re5") (pin "2") (pinfunction "2_2") (pintype "passive"))
      (node (ref "Re6") (pin "2") (pinfunction "2_2") (pintype "passive"))
      (node (ref "Re7") (pin "2") (pinfunction "2_2") (pintype "passive"))
      (node (ref "Re8") (pin "2") (pinfunction "2_2") (pintype "passive"))
      (node (ref "Re9") (pin "2") (pinfunction "2_2") (pintype "passive"))
      (node (ref "U1") (pin "8") (pinfunction "E/D_8") (pintype "input"))
      (node (ref "U10") (pin "8") (pinfunction "E/D_8") (pintype "input"))
      (node (ref "U11") (pin "8") (pinfunction "E/D_8") (pintype "input"))
      (node (ref "U12") (pin "8") (pinfunction "E/D_8") (pintype "input"))
      (node (ref "U13") (pin "8") (pinfunction "E/D_8") (pintype "input"))
      (node (ref "U14") (pin "8") (pinfunction "E/D_8") (pintype "input"))
      (node (ref "U15") (pin "8") (pinfunction "E/D_8") (pintype "input"))
      (node (ref "U16") (pin "8") (pinfunction "E/D_8") (pintype "input"))
      (node (ref "U17") (pin "8") (pinfunction "E/D_8") (pintype "input"))
      (node (ref "U18") (pin "8") (pinfunction "E/D_8") (pintype "input"))
      (node (ref "U19") (pin "8") (pinfunction "E/D_8") (pintype "input"))
      (node (ref "U2") (pin "8") (pinfunction "E/D_8") (pintype "input"))
      (node (ref "U20") (pin "8") (pinfunction "E/D_8") (pintype "input"))
      (node (ref "U3") (pin "8") (pinfunction "E/D_8") (pintype "input"))
      (node (ref "U4") (pin "8") (pinfunction "E/D_8") (pintype "input"))
      (node (ref "U5") (pin "8") (pinfunction "E/D_8") (pintype "input"))
      (node (ref "U6") (pin "8") (pinfunction "E/D_8") (pintype "input"))
      (node (ref "U7") (pin "8") (pinfunction "E/D_8") (pintype "input"))
      (node (ref "U8") (pin "8") (pinfunction "E/D_8") (pintype "input"))
      (node (ref "U9") (pin "8") (pinfunction "E/D_8") (pintype "input"))
    )
    (net (code "2") (name "+50V") (class "Default")
      (node (ref "Cd101") (pin "2") (pinfunction "2_2") (pintype "passive"))
      (node (ref "Cd102") (pin "1") (pinfunction "1_1") (pintype "passive"))
      (node (ref "Cd11") (pin "2") (pinfunction "2_2") (pintype "passive"))
      (node (ref "Cd111") (pin "2") (pinfunction "2_2") (pintype "passive"))
      (node (ref "Cd112") (pin "1") (pinfunction "1_1") (pintype "passive"))
      (node (ref "Cd12") (pin "1") (pinfunction "1_1") (pintype "passive"))
      (node (ref "Cd121") (pin "2") (pinfunction "2_2") (pintype "passive"))
      (node (ref "Cd122") (pin "1") (pinfunction "1_1") (pintype "passive"))
      (node (ref "Cd131") (pin "2") (pinfunction "2_2") (pintype "passive"))
      (node (ref "Cd132") (pin "1") (pinfunction "1_1") (pintype "passive"))
      (node (ref "Cd141") (pin "2") (pinfunction "2_2") (pintype "passive"))
      (node (ref "Cd142") (pin "1") (pinfunction "1_1") (pintype "passive"))
      (node (ref "Cd151") (pin "2") (pinfunction "2_2") (pintype "passive"))
      (node (ref "Cd152") (pin "1") (pinfunction "1_1") (pintype "passive"))
      (node (ref "Cd161") (pin "2") (pinfunction "2_2") (pintype "passive"))
      (node (ref "Cd162") (pin "1") (pinfunction "1_1") (pintype "passive"))
      (node (ref "Cd171") (pin "2") (pinfunction "2_2") (pintype "passive"))
      (node (ref "Cd172") (pin "1") (pinfunction "1_1") (pintype "passive"))
      (node (ref "Cd181") (pin "2") (pinfunction "2_2") (pintype "passive"))
      (node (ref "Cd182") (pin "1") (pinfunction "1_1") (pintype "passive"))
      (node (ref "Cd191") (pin "2") (pinfunction "2_2") (pintype "passive"))
      (node (ref "Cd192") (pin "1") (pinfunction "1_1") (pintype "passive"))
      (node (ref "Cd201") (pin "2") (pinfunction "2_2") (pintype "passive"))
      (node (ref "Cd202") (pin "1") (pinfunction "1_1") (pintype "passive"))
      (node (ref "Cd21") (pin "2") (pinfunction "2_2") (pintype "passive"))
      (node (ref "Cd22") (pin "1") (pinfunction "1_1") (pintype "passive"))
      (node (ref "Cd31") (pin "2") (pinfunction "2_2") (pintype "passive"))
      (node (ref "Cd32") (pin "1") (pinfunction "1_1") (pintype "passive"))
      (node (ref "Cd41") (pin "2") (pinfunction "2_2") (pintype "passive"))
      (node (ref "Cd42") (pin "1") (pinfunction "1_1") (pintype "passive"))
      (node (ref "Cd51") (pin "2") (pinfunction "2_2") (pintype "passive"))
      (node (ref "Cd52") (pin "1") (pinfunction "1_1") (pintype "passive"))
      (node (ref "Cd61") (pin "2") (pinfunction "2_2") (pintype "passive"))
      (node (ref "Cd62") (pin "1") (pinfunction "1_1") (pintype "passive"))
      (node (ref "Cd71") (pin "2") (pinfunction "2_2") (pintype "passive"))
      (node (ref "Cd72") (pin "1") (pinfunction "1_1") (pintype "passive"))
      (node (ref "Cd81") (pin "2") (pinfunction "2_2") (pintype "passive"))
      (node (ref "Cd82") (pin "1") (pinfunction "1_1") (pintype "passive"))
      (node (ref "Cd91") (pin "2") (pinfunction "2_2") (pintype "passive"))
      (node (ref "Cd92") (pin "1") (pinfunction "1_1") (pintype "passive"))
      (node (ref "U1") (pin "7") (pinfunction "V+_7") (pintype "power_in"))
      (node (ref "U10") (pin "7") (pinfunction "V+_7") (pintype "power_in"))
      (node (ref "U11") (pin "7") (pinfunction "V+_7") (pintype "power_in"))
      (node (ref "U12") (pin "7") (pinfunction "V+_7") (pintype "power_in"))
      (node (ref "U13") (pin "7") (pinfunction "V+_7") (pintype "power_in"))
      (node (ref "U14") (pin "7") (pinfunction "V+_7") (pintype "power_in"))
      (node (ref "U15") (pin "7") (pinfunction "V+_7") (pintype "power_in"))
      (node (ref "U16") (pin "7") (pinfunction "V+_7") (pintype "power_in"))
      (node (ref "U17") (pin "7") (pinfunction "V+_7") (pintype "power_in"))
      (node (ref "U18") (pin "7") (pinfunction "V+_7") (pintype "power_in"))
      (node (ref "U19") (pin "7") (pinfunction "V+_7") (pintype "power_in"))
      (node (ref "U2") (pin "7") (pinfunction "V+_7") (pintype "power_in"))
      (node (ref "U20") (pin "7") (pinfunction "V+_7") (pintype "power_in"))
      (node (ref "U3") (pin "7") (pinfunction "V+_7") (pintype "power_in"))
      (node (ref "U4") (pin "7") (pinfunction "V+_7") (pintype "power_in"))
      (node (ref "U5") (pin "7") (pinfunction "V+_7") (pintype "power_in"))
      (node (ref "U6") (pin "7") (pinfunction "V+_7") (pintype "power_in"))
      (node (ref "U7") (pin "7") (pinfunction "V+_7") (pintype "power_in"))
      (node (ref "U8") (pin "7") (pinfunction "V+_7") (pintype "power_in"))
      (node (ref "U9") (pin "7") (pinfunction "V+_7") (pintype "power_in"))
    )
    (net (code "3") (name "-50V") (class "Default")
      (node (ref "Cd103") (pin "2") (pinfunction "2_2") (pintype "passive"))
      (node (ref "Cd104") (pin "1") (pinfunction "1_1") (pintype "passive"))
      (node (ref "Cd113") (pin "2") (pinfunction "2_2") (pintype "passive"))
      (node (ref "Cd114") (pin "1") (pinfunction "1_1") (pintype "passive"))
      (node (ref "Cd123") (pin "2") (pinfunction "2_2") (pintype "passive"))
      (node (ref "Cd124") (pin "1") (pinfunction "1_1") (pintype "passive"))
      (node (ref "Cd13") (pin "2") (pinfunction "2_2") (pintype "passive"))
      (node (ref "Cd133") (pin "2") (pinfunction "2_2") (pintype "passive"))
      (node (ref "Cd134") (pin "1") (pinfunction "1_1") (pintype "passive"))
      (node (ref "Cd14") (pin "1") (pinfunction "1_1") (pintype "passive"))
      (node (ref "Cd143") (pin "2") (pinfunction "2_2") (pintype "passive"))
      (node (ref "Cd144") (pin "1") (pinfunction "1_1") (pintype "passive"))
      (node (ref "Cd153") (pin "2") (pinfunction "2_2") (pintype "passive"))
      (node (ref "Cd154") (pin "1") (pinfunction "1_1") (pintype "passive"))
      (node (ref "Cd163") (pin "2") (pinfunction "2_2") (pintype "passive"))
      (node (ref "Cd164") (pin "1") (pinfunction "1_1") (pintype "passive"))
      (node (ref "Cd173") (pin "2") (pinfunction "2_2") (pintype "passive"))
      (node (ref "Cd174") (pin "1") (pinfunction "1_1") (pintype "passive"))
      (node (ref "Cd183") (pin "2") (pinfunction "2_2") (pintype "passive"))
      (node (ref "Cd184") (pin "1") (pinfunction "1_1") (pintype "passive"))
      (node (ref "Cd193") (pin "2") (pinfunction "2_2") (pintype "passive"))
      (node (ref "Cd194") (pin "1") (pinfunction "1_1") (pintype "passive"))
      (node (ref "Cd203") (pin "2") (pinfunction "2_2") (pintype "passive"))
      (node (ref "Cd204") (pin "1") (pinfunction "1_1") (pintype "passive"))
      (node (ref "Cd23") (pin "2") (pinfunction "2_2") (pintype "passive"))
      (node (ref "Cd24") (pin "1") (pinfunction "1_1") (pintype "passive"))
      (node (ref "Cd33") (pin "2") (pinfunction "2_2") (pintype "passive"))
      (node (ref "Cd34") (pin "1") (pinfunction "1_1") (pintype "passive"))
      (node (ref "Cd43") (pin "2") (pinfunction "2_2") (pintype "passive"))
      (node (ref "Cd44") (pin "1") (pinfunction "1_1") (pintype "passive"))
      (node (ref "Cd53") (pin "2") (pinfunction "2_2") (pintype "passive"))
      (node (ref "Cd54") (pin "1") (pinfunction "1_1") (pintype "passive"))
      (node (ref "Cd63") (pin "2") (pinfunction "2_2") (pintype "passive"))
      (node (ref "Cd64") (pin "1") (pinfunction "1_1") (pintype "passive"))
      (node (ref "Cd73") (pin "2") (pinfunction "2_2") (pintype "passive"))
      (node (ref "Cd74") (pin "1") (pinfunction "1_1") (pintype "passive"))
      (node (ref "Cd83") (pin "2") (pinfunction "2_2") (pintype "passive"))
      (node (ref "Cd84") (pin "1") (pinfunction "1_1") (pintype "passive"))
      (node (ref "Cd93") (pin "2") (pinfunction "2_2") (pintype "passive"))
      (node (ref "Cd94") (pin "1") (pinfunction "1_1") (pintype "passive"))
      (node (ref "U1") (pin "4") (pinfunction "V-_4") (pintype "power_in"))
      (node (ref "U10") (pin "4") (pinfunction "V-_4") (pintype "power_in"))
      (node (ref "U11") (pin "4") (pinfunction "V-_4") (pintype "power_in"))
      (node (ref "U12") (pin "4") (pinfunction "V-_4") (pintype "power_in"))
      (node (ref "U13") (pin "4") (pinfunction "V-_4") (pintype "power_in"))
      (node (ref "U14") (pin "4") (pinfunction "V-_4") (pintype "power_in"))
      (node (ref "U15") (pin "4") (pinfunction "V-_4") (pintype "power_in"))
      (node (ref "U16") (pin "4") (pinfunction "V-_4") (pintype "power_in"))
      (node (ref "U17") (pin "4") (pinfunction "V-_4") (pintype "power_in"))
      (node (ref "U18") (pin "4") (pinfunction "V-_4") (pintype "power_in"))
      (node (ref "U19") (pin "4") (pinfunction "V-_4") (pintype "power_in"))
      (node (ref "U2") (pin "4") (pinfunction "V-_4") (pintype "power_in"))
      (node (ref "U20") (pin "4") (pinfunction "V-_4") (pintype "power_in"))
      (node (ref "U3") (pin "4") (pinfunction "V-_4") (pintype "power_in"))
      (node (ref "U4") (pin "4") (pinfunction "V-_4") (pintype "power_in"))
      (node (ref "U5") (pin "4") (pinfunction "V-_4") (pintype "power_in"))
      (node (ref "U6") (pin "4") (pinfunction "V-_4") (pintype "power_in"))
      (node (ref "U7") (pin "4") (pinfunction "V-_4") (pintype "power_in"))
      (node (ref "U8") (pin "4") (pinfunction "V-_4") (pintype "power_in"))
      (node (ref "U9") (pin "4") (pinfunction "V-_4") (pintype "power_in"))
    )
    (net (code "4") (name "CH1A") (class "Default")
      (node (ref "Rf1") (pin "2") (pinfunction "2_2") (pintype "passive"))
      (node (ref "T1") (pin "3") (pinfunction "DC_3") (pintype "input"))
      (node (ref "U1") (pin "6") (pinfunction "OUT_6") (pintype "output"))
    )
    (net (code "5") (name "CH1F") (class "Default")
      (node (ref "C1") (pin "2") (pinfunction "2_2") (pintype "passive"))
      (node (ref "R1") (pin "2") (pinfunction "2_2") (pintype "passive"))
      (node (ref "U1") (pin "3") (pinfunction "IN+_3") (pintype "input"))
    )
    (net (code "6") (name "CH1IN") (class "Default")
      (node (ref "JIN") (pin "1") (pinfunction "Z0_1") (pintype "passive"))
      (node (ref "R1") (pin "1") (pinfunction "1_1") (pintype "passive"))
    )
    (net (code "7") (name "CH1OUT") (class "Default")
      (node (ref "JOUT") (pin "1") (pinfunction "1_1") (pintype "passive"))
      (node (ref "T1") (pin "12") (pinfunction "DC+RF_12") (pintype "output"))
    )
    (net (code "8") (name "CH2A") (class "Default")
      (node (ref "JOUT") (pin "2") (pinfunction "2_2") (pintype "passive"))
      (node (ref "Rf2") (pin "2") (pinfunction "2_2") (pintype "passive"))
      (node (ref "U2") (pin "6") (pinfunction "OUT_6") (pintype "output"))
    )
    (net (code "9") (name "CH2F") (class "Default")
      (node (ref "C2") (pin "2") (pinfunction "2_2") (pintype "passive"))
      (node (ref "R2") (pin "2") (pinfunction "2_2") (pintype "passive"))
      (node (ref "U2") (pin "3") (pinfunction "IN+_3") (pintype "input"))
    )
    (net (code "10") (name "CH2IN") (class "Default")
      (node (ref "JIN") (pin "2") (pinfunction "Z1_2") (pintype "passive"))
      (node (ref "R2") (pin "1") (pinfunction "1_1") (pintype "passive"))
    )
    (net (code "11") (name "CH3A") (class "Default")
      (node (ref "Rf3") (pin "2") (pinfunction "2_2") (pintype "passive"))
      (node (ref "T3") (pin "3") (pinfunction "DC_3") (pintype "input"))
      (node (ref "U3") (pin "6") (pinfunction "OUT_6") (pintype "output"))
    )
    (net (code "12") (name "CH3F") (class "Default")
      (node (ref "C3") (pin "2") (pinfunction "2_2") (pintype "passive"))
      (node (ref "R3") (pin "2") (pinfunction "2_2") (pintype "passive"))
      (node (ref "U3") (pin "3") (pinfunction "IN+_3") (pintype "input"))
    )
    (net (code "13") (name "CH3IN") (class "Default")
      (node (ref "JIN") (pin "3") (pinfunction "Z2_3") (pintype "passive"))
      (node (ref "R3") (pin "1") (pinfunction "1_1") (pintype "passive"))
    )
    (net (code "14") (name "CH3OUT") (class "Default")
      (node (ref "JOUT") (pin "3") (pinfunction "3_3") (pintype "passive"))
      (node (ref "T3") (pin "12") (pinfunction "DC+RF_12") (pintype "output"))
    )
    (net (code "15") (name "CH4A") (class "Default")
      (node (ref "JOUT") (pin "4") (pinfunction "4_4") (pintype "passive"))
      (node (ref "Rf4") (pin "2") (pinfunction "2_2") (pintype "passive"))
      (node (ref "U4") (pin "6") (pinfunction "OUT_6") (pintype "output"))
    )
    (net (code "16") (name "CH4F") (class "Default")
      (node (ref "C4") (pin "2") (pinfunction "2_2") (pintype "passive"))
      (node (ref "R4") (pin "2") (pinfunction "2_2") (pintype "passive"))
      (node (ref "U4") (pin "3") (pinfunction "IN+_3") (pintype "input"))
    )
    (net (code "17") (name "CH4IN") (class "Default")
      (node (ref "JIN") (pin "4") (pinfunction "Z3_4") (pintype "passive"))
      (node (ref "R4") (pin "1") (pinfunction "1_1") (pintype "passive"))
    )
    (net (code "18") (name "CH5A") (class "Default")
      (node (ref "JOUT") (pin "5") (pinfunction "5_5") (pintype "passive"))
      (node (ref "Rf5") (pin "2") (pinfunction "2_2") (pintype "passive"))
      (node (ref "U5") (pin "6") (pinfunction "OUT_6") (pintype "output"))
    )
    (net (code "19") (name "CH5F") (class "Default")
      (node (ref "C5") (pin "2") (pinfunction "2_2") (pintype "passive"))
      (node (ref "R5") (pin "2") (pinfunction "2_2") (pintype "passive"))
      (node (ref "U5") (pin "3") (pinfunction "IN+_3") (pintype "input"))
    )
    (net (code "20") (name "CH5IN") (class "Default")
      (node (ref "JIN") (pin "5") (pinfunction "Z4_5") (pintype "passive"))
      (node (ref "R5") (pin "1") (pinfunction "1_1") (pintype "passive"))
    )
    (net (code "21") (name "CH6A") (class "Default")
      (node (ref "JOUT") (pin "9") (pinfunction "9_9") (pintype "passive"))
      (node (ref "Rf6") (pin "2") (pinfunction "2_2") (pintype "passive"))
      (node (ref "U6") (pin "6") (pinfunction "OUT_6") (pintype "output"))
    )
    (net (code "22") (name "CH6F") (class "Default")
      (node (ref "C6") (pin "2") (pinfunction "2_2") (pintype "passive"))
      (node (ref "R6") (pin "2") (pinfunction "2_2") (pintype "passive"))
      (node (ref "U6") (pin "3") (pinfunction "IN+_3") (pintype "input"))
    )
    (net (code "23") (name "CH6IN") (class "Default")
      (node (ref "JIN") (pin "6") (pinfunction "Z5_6") (pintype "passive"))
      (node (ref "R6") (pin "1") (pinfunction "1_1") (pintype "passive"))
    )
    (net (code "24") (name "CH7A") (class "Default")
      (node (ref "JOUT") (pin "10") (pinfunction "10_10") (pintype "passive"))
      (node (ref "Rf7") (pin "2") (pinfunction "2_2") (pintype "passive"))
      (node (ref "U7") (pin "6") (pinfunction "OUT_6") (pintype "output"))
    )
    (net (code "25") (name "CH7F") (class "Default")
      (node (ref "C7") (pin "2") (pinfunction "2_2") (pintype "passive"))
      (node (ref "R7") (pin "2") (pinfunction "2_2") (pintype "passive"))
      (node (ref "U7") (pin "3") (pinfunction "IN+_3") (pintype "input"))
    )
    (net (code "26") (name "CH7IN") (class "Default")
      (node (ref "JIN") (pin "7") (pinfunction "Z6_7") (pintype "passive"))
      (node (ref "R7") (pin "1") (pinfunction "1_1") (pintype "passive"))
    )
    (net (code "27") (name "CH8A") (class "Default")
      (node (ref "Rf8") (pin "2") (pinfunction "2_2") (pintype "passive"))
      (node (ref "T8") (pin "3") (pinfunction "DC_3") (pintype "input"))
      (node (ref "U8") (pin "6") (pinfunction "OUT_6") (pintype "output"))
    )
    (net (code "28") (name "CH8F") (class "Default")
      (node (ref "C8") (pin "2") (pinfunction "2_2") (pintype "passive"))
      (node (ref "R8") (pin "2") (pinfunction "2_2") (pintype "passive"))
      (node (ref "U8") (pin "3") (pinfunction "IN+_3") (pintype "input"))
    )
    (net (code "29") (name "CH8IN") (class "Default")
      (node (ref "JIN") (pin "8") (pinfunction "Z7_8") (pintype "passive"))
      (node (ref "R8") (pin "1") (pinfunction "1_1") (pintype "passive"))
    )
    (net (code "30") (name "CH8OUT") (class "Default")
      (node (ref "JOUT") (pin "11") (pinfunction "11_11") (pintype "passive"))
      (node (ref "T8") (pin "12") (pinfunction "DC+RF_12") (pintype "output"))
    )
    (net (code "31") (name "CH9A") (class "Default")
      (node (ref "JOUT") (pin "12") (pinfunction "12_12") (pintype "passive"))
      (node (ref "Rf9") (pin "2") (pinfunction "2_2") (pintype "passive"))
      (node (ref "U9") (pin "6") (pinfunction "OUT_6") (pintype "output"))
    )
    (net (code "32") (name "CH9F") (class "Default")
      (node (ref "C9") (pin "2") (pinfunction "2_2") (pintype "passive"))
      (node (ref "R9") (pin "2") (pinfunction "2_2") (pintype "passive"))
      (node (ref "U9") (pin "3") (pinfunction "IN+_3") (pintype "input"))
    )
    (net (code "33") (name "CH9IN") (class "Default")
      (node (ref "JIN") (pin "9") (pinfunction "Z8_9") (pintype "passive"))
      (node (ref "R9") (pin "1") (pinfunction "1_1") (pintype "passive"))
    )
    (net (code "34") (name "CH10A") (class "Default")
      (node (ref "Rf10") (pin "2") (pinfunction "2_2") (pintype "passive"))
      (node (ref "T10") (pin "3") (pinfunction "DC_3") (pintype "input"))
      (node (ref "U10") (pin "6") (pinfunction "OUT_6") (pintype "output"))
    )
    (net (code "35") (name "CH10F") (class "Default")
      (node (ref "C10") (pin "2") (pinfunction "2_2") (pintype "passive"))
      (node (ref "R10") (pin "2") (pinfunction "2_2") (pintype "passive"))
      (node (ref "U10") (pin "3") (pinfunction "IN+_3") (pintype "input"))
    )
    (net (code "36") (name "CH10IN") (class "Default")
      (node (ref "JIN") (pin "10") (pinfunction "Z9_10") (pintype "passive"))
      (node (ref "R10") (pin "1") (pinfunction "1_1") (pintype "passive"))
    )
    (net (code "37") (name "CH10OUT") (class "Default")
      (node (ref "JOUT") (pin "13") (pinfunction "13_13") (pintype "passive"))
      (node (ref "T10") (pin "12") (pinfunction "DC+RF_12") (pintype "output"))
    )
    (net (code "38") (name "CH11A") (class "Default")
      (node (ref "JOUT") (pin "14") (pinfunction "14_14") (pintype "passive"))
      (node (ref "Rf11") (pin "2") (pinfunction "2_2") (pintype "passive"))
      (node (ref "U11") (pin "6") (pinfunction "OUT_6") (pintype "output"))
    )
    (net (code "39") (name "CH11F") (class "Default")
      (node (ref "C11") (pin "2") (pinfunction "2_2") (pintype "passive"))
      (node (ref "R11") (pin "2") (pinfunction "2_2") (pintype "passive"))
      (node (ref "U11") (pin "3") (pinfunction "IN+_3") (pintype "input"))
    )
    (net (code "40") (name "CH11IN") (class "Default")
      (node (ref "JIN") (pin "11") (pinfunction "Z10_11") (pintype "passive"))
      (node (ref "R11") (pin "1") (pinfunction "1_1") (pintype "passive"))
    )
    (net (code "41") (name "CH12A") (class "Default")
      (node (ref "Rf12") (pin "2") (pinfunction "2_2") (pintype "passive"))
      (node (ref "T12") (pin "3") (pinfunction "DC_3") (pintype "input"))
      (node (ref "U12") (pin "6") (pinfunction "OUT_6") (pintype "output"))
    )
    (net (code "42") (name "CH12F") (class "Default")
      (node (ref "C12") (pin "2") (pinfunction "2_2") (pintype "passive"))
      (node (ref "R12") (pin "2") (pinfunction "2_2") (pintype "passive"))
      (node (ref "U12") (pin "3") (pinfunction "IN+_3") (pintype "input"))
    )
    (net (code "43") (name "CH12IN") (class "Default")
      (node (ref "JIN") (pin "12") (pinfunction "Z11_12") (pintype "passive"))
      (node (ref "R12") (pin "1") (pinfunction "1_1") (pintype "passive"))
    )
    (net (code "44") (name "CH12OUT") (class "Default")
      (node (ref "JOUT") (pin "15") (pinfunction "15_15") (pintype "passive"))
      (node (ref "T12") (pin "12") (pinfunction "DC+RF_12") (pintype "output"))
    )
    (net (code "45") (name "CH13A") (class "Default")
      (node (ref "JOUT") (pin "16") (pinfunction "16_16") (pintype "passive"))
      (node (ref "Rf13") (pin "2") (pinfunction "2_2") (pintype "passive"))
      (node (ref "U13") (pin "6") (pinfunction "OUT_6") (pintype "output"))
    )
    (net (code "46") (name "CH13F") (class "Default")
      (node (ref "C13") (pin "2") (pinfunction "2_2") (pintype "passive"))
      (node (ref "R13") (pin "2") (pinfunction "2_2") (pintype "passive"))
      (node (ref "U13") (pin "3") (pinfunction "IN+_3") (pintype "input"))
    )
    (net (code "47") (name "CH13IN") (class "Default")
      (node (ref "JIN") (pin "13") (pinfunction "Z12_13") (pintype "passive"))
      (node (ref "R13") (pin "1") (pinfunction "1_1") (pintype "passive"))
    )
    (net (code "48") (name "CH14A") (class "Default")
      (node (ref "JOUT") (pin "17") (pinfunction "17_17") (pintype "passive"))
      (node (ref "Rf14") (pin "2") (pinfunction "2_2") (pintype "passive"))
      (node (ref "U14") (pin "6") (pinfunction "OUT_6") (pintype "output"))
    )
    (net (code "49") (name "CH14F") (class "Default")
      (node (ref "C14") (pin "2") (pinfunction "2_2") (pintype "passive"))
      (node (ref "R14") (pin "2") (pinfunction "2_2") (pintype "passive"))
      (node (ref "U14") (pin "3") (pinfunction "IN+_3") (pintype "input"))
    )
    (net (code "50") (name "CH14IN") (class "Default")
      (node (ref "JIN") (pin "14") (pinfunction "Z13_14") (pintype "passive"))
      (node (ref "R14") (pin "1") (pinfunction "1_1") (pintype "passive"))
    )
    (net (code "51") (name "CH15A") (class "Default")
      (node (ref "JOUT") (pin "18") (pinfunction "18_18") (pintype "passive"))
      (node (ref "Rf15") (pin "2") (pinfunction "2_2") (pintype "passive"))
      (node (ref "U15") (pin "6") (pinfunction "OUT_6") (pintype "output"))
    )
    (net (code "52") (name "CH15F") (class "Default")
      (node (ref "C15") (pin "2") (pinfunction "2_2") (pintype "passive"))
      (node (ref "R15") (pin "2") (pinfunction "2_2") (pintype "passive"))
      (node (ref "U15") (pin "3") (pinfunction "IN+_3") (pintype "input"))
    )
    (net (code "53") (name "CH15IN") (class "Default")
      (node (ref "JIN") (pin "15") (pinfunction "Z14_15") (pintype "passive"))
      (node (ref "R15") (pin "1") (pinfunction "1_1") (pintype "passive"))
    )
    (net (code "54") (name "CH16A") (class "Default")
      (node (ref "JOUT") (pin "21") (pinfunction "21_21") (pintype "passive"))
      (node (ref "Rf16") (pin "2") (pinfunction "2_2") (pintype "passive"))
      (node (ref "U16") (pin "6") (pinfunction "OUT_6") (pintype "output"))
    )
    (net (code "55") (name "CH16F") (class "Default")
      (node (ref "C16") (pin "2") (pinfunction "2_2") (pintype "passive"))
      (node (ref "R16") (pin "2") (pinfunction "2_2") (pintype "passive"))
      (node (ref "U16") (pin "3") (pinfunction "IN+_3") (pintype "input"))
    )
    (net (code "56") (name "CH16IN") (class "Default")
      (node (ref "JIN") (pin "16") (pinfunction "Z15_16") (pintype "passive"))
      (node (ref "R16") (pin "1") (pinfunction "1_1") (pintype "passive"))
    )
    (net (code "57") (name "CH17A") (class "Default")
      (node (ref "JOUT") (pin "22") (pinfunction "22_22") (pintype "passive"))
      (node (ref "Rf17") (pin "2") (pinfunction "2_2") (pintype "passive"))
      (node (ref "U17") (pin "6") (pinfunction "OUT_6") (pintype "output"))
    )
    (net (code "58") (name "CH17F") (class "Default")
      (node (ref "C17") (pin "2") (pinfunction "2_2") (pintype "passive"))
      (node (ref "R17") (pin "2") (pinfunction "2_2") (pintype "passive"))
      (node (ref "U17") (pin "3") (pinfunction "IN+_3") (pintype "input"))
    )
    (net (code "59") (name "CH17IN") (class "Default")
      (node (ref "JIN") (pin "19") (pinfunction "Z16_19") (pintype "passive"))
      (node (ref "R17") (pin "1") (pinfunction "1_1") (pintype "passive"))
    )
    (net (code "60") (name "CH18A") (class "Default")
      (node (ref "JOUT") (pin "23") (pinfunction "23_23") (pintype "passive"))
      (node (ref "Rf18") (pin "2") (pinfunction "2_2") (pintype "passive"))
      (node (ref "U18") (pin "6") (pinfunction "OUT_6") (pintype "output"))
    )
    (net (code "61") (name "CH18F") (class "Default")
      (node (ref "C18") (pin "2") (pinfunction "2_2") (pintype "passive"))
      (node (ref "R18") (pin "2") (pinfunction "2_2") (pintype "passive"))
      (node (ref "U18") (pin "3") (pinfunction "IN+_3") (pintype "input"))
    )
    (net (code "62") (name "CH18IN") (class "Default")
      (node (ref "JIN") (pin "20") (pinfunction "Z17_20") (pintype "passive"))
      (node (ref "R18") (pin "1") (pinfunction "1_1") (pintype "passive"))
    )
    (net (code "63") (name "CH19A") (class "Default")
      (node (ref "Rf19") (pin "2") (pinfunction "2_2") (pintype "passive"))
      (node (ref "T19") (pin "3") (pinfunction "DC_3") (pintype "input"))
      (node (ref "U19") (pin "6") (pinfunction "OUT_6") (pintype "output"))
    )
    (net (code "64") (name "CH19F") (class "Default")
      (node (ref "C19") (pin "2") (pinfunction "2_2") (pintype "passive"))
      (node (ref "R19") (pin "2") (pinfunction "2_2") (pintype "passive"))
      (node (ref "U19") (pin "3") (pinfunction "IN+_3") (pintype "input"))
    )
    (net (code "65") (name "CH19IN") (class "Default")
      (node (ref "JIN") (pin "21") (pinfunction "Z18_21") (pintype "passive"))
      (node (ref "R19") (pin "1") (pinfunction "1_1") (pintype "passive"))
    )
    (net (code "66") (name "CH19OUT") (class "Default")
      (node (ref "JOUT") (pin "24") (pinfunction "24_24") (pintype "passive"))
      (node (ref "T19") (pin "12") (pinfunction "DC+RF_12") (pintype "output"))
    )
    (net (code "67") (name "CH20A") (class "Default")
      (node (ref "JOUT") (pin "25") (pinfunction "25_25") (pintype "passive"))
      (node (ref "Rf20") (pin "2") (pinfunction "2_2") (pintype "passive"))
      (node (ref "U20") (pin "6") (pinfunction "OUT_6") (pintype "output"))
    )
    (net (code "68") (name "CH20F") (class "Default")
      (node (ref "C20") (pin "2") (pinfunction "2_2") (pintype "passive"))
      (node (ref "R20") (pin "2") (pinfunction "2_2") (pintype "passive"))
      (node (ref "U20") (pin "3") (pinfunction "IN+_3") (pintype "input"))
    )
    (net (code "69") (name "CH20IN") (class "Default")
      (node (ref "JIN") (pin "22") (pinfunction "Z19_22") (pintype "passive"))
      (node (ref "R20") (pin "1") (pinfunction "1_1") (pintype "passive"))
    )
    (net (code "70") (name "GND") (class "Default")
      (node (ref "C1") (pin "1") (pinfunction "1_1") (pintype "passive"))
      (node (ref "C10") (pin "1") (pinfunction "1_1") (pintype "passive"))
      (node (ref "C11") (pin "1") (pinfunction "1_1") (pintype "passive"))
      (node (ref "C12") (pin "1") (pinfunction "1_1") (pintype "passive"))
      (node (ref "C13") (pin "1") (pinfunction "1_1") (pintype "passive"))
      (node (ref "C14") (pin "1") (pinfunction "1_1") (pintype "passive"))
      (node (ref "C15") (pin "1") (pinfunction "1_1") (pintype "passive"))
      (node (ref "C16") (pin "1") (pinfunction "1_1") (pintype "passive"))
      (node (ref "C17") (pin "1") (pinfunction "1_1") (pintype "passive"))
      (node (ref "C18") (pin "1") (pinfunction "1_1") (pintype "passive"))
      (node (ref "C19") (pin "1") (pinfunction "1_1") (pintype "passive"))
      (node (ref "C2") (pin "1") (pinfunction "1_1") (pintype "passive"))
      (node (ref "C20") (pin "1") (pinfunction "1_1") (pintype "passive"))
      (node (ref "C3") (pin "1") (pinfunction "1_1") (pintype "passive"))
      (node (ref "C4") (pin "1") (pinfunction "1_1") (pintype "passive"))
      (node (ref "C5") (pin "1") (pinfunction "1_1") (pintype "passive"))
      (node (ref "C6") (pin "1") (pinfunction "1_1") (pintype "passive"))
      (node (ref "C7") (pin "1") (pinfunction "1_1") (pintype "passive"))
      (node (ref "C8") (pin "1") (pinfunction "1_1") (pintype "passive"))
      (node (ref "C9") (pin "1") (pinfunction "1_1") (pintype "passive"))
      (node (ref "Cd101") (pin "1") (pinfunction "1_1") (pintype "passive"))
      (node (ref "Cd102") (pin "2") (pinfunction "2_2") (pintype "passive"))
      (node (ref "Cd103") (pin "1") (pinfunction "1_1") (pintype "passive"))
      (node (ref "Cd104") (pin "2") (pinfunction "2_2") (pintype "passive"))
      (node (ref "Cd11") (pin "1") (pinfunction "1_1") (pintype "passive"))
      (node (ref "Cd111") (pin "1") (pinfunction "1_1") (pintype "passive"))
      (node (ref "Cd112") (pin "2") (pinfunction "2_2") (pintype "passive"))
      (node (ref "Cd113") (pin "1") (pinfunction "1_1") (pintype "passive"))
      (node (ref "Cd114") (pin "2") (pinfunction "2_2") (pintype "passive"))
      (node (ref "Cd12") (pin "2") (pinfunction "2_2") (pintype "passive"))
      (node (ref "Cd121") (pin "1") (pinfunction "1_1") (pintype "passive"))
      (node (ref "Cd122") (pin "2") (pinfunction "2_2") (pintype "passive"))
      (node (ref "Cd123") (pin "1") (pinfunction "1_1") (pintype "passive"))
      (node (ref "Cd124") (pin "2") (pinfunction "2_2") (pintype "passive"))
      (node (ref "Cd13") (pin "1") (pinfunction "1_1") (pintype "passive"))
      (node (ref "Cd131") (pin "1") (pinfunction "1_1") (pintype "passive"))
      (node (ref "Cd132") (pin "2") (pinfunction "2_2") (pintype "passive"))
      (node (ref "Cd133") (pin "1") (pinfunction "1_1") (pintype "passive"))
      (node (ref "Cd134") (pin "2") (pinfunction "2_2") (pintype "passive"))
      (node (ref "Cd14") (pin "2") (pinfunction "2_2") (pintype "passive"))
      (node (ref "Cd141") (pin "1") (pinfunction "1_1") (pintype "passive"))
      (node (ref "Cd142") (pin "2") (pinfunction "2_2") (pintype "passive"))
      (node (ref "Cd143") (pin "1") (pinfunction "1_1") (pintype "passive"))
      (node (ref "Cd144") (pin "2") (pinfunction "2_2") (pintype "passive"))
      (node (ref "Cd151") (pin "1") (pinfunction "1_1") (pintype "passive"))
      (node (ref "Cd152") (pin "2") (pinfunction "2_2") (pintype "passive"))
      (node (ref "Cd153") (pin "1") (pinfunction "1_1") (pintype "passive"))
      (node (ref "Cd154") (pin "2") (pinfunction "2_2") (pintype "passive"))
      (node (ref "Cd161") (pin "1") (pinfunction "1_1") (pintype "passive"))
      (node (ref "Cd162") (pin "2") (pinfunction "2_2") (pintype "passive"))
      (node (ref "Cd163") (pin "1") (pinfunction "1_1") (pintype "passive"))
      (node (ref "Cd164") (pin "2") (pinfunction "2_2") (pintype "passive"))
      (node (ref "Cd171") (pin "1") (pinfunction "1_1") (pintype "passive"))
      (node (ref "Cd172") (pin "2") (pinfunction "2_2") (pintype "passive"))
      (node (ref "Cd173") (pin "1") (pinfunction "1_1") (pintype "passive"))
      (node (ref "Cd174") (pin "2") (pinfunction "2_2") (pintype "passive"))
      (node (ref "Cd181") (pin "1") (pinfunction "1_1") (pintype "passive"))
      (node (ref "Cd182") (pin "2") (pinfunction "2_2") (pintype "passive"))
      (node (ref "Cd183") (pin "1") (pinfunction "1_1") (pintype "passive"))
      (node (ref "Cd184") (pin "2") (pinfunction "2_2") (pintype "passive"))
      (node (ref "Cd191") (pin "1") (pinfunction "1_1") (pintype "passive"))
      (node (ref "Cd192") (pin "2") (pinfunction "2_2") (pintype "passive"))
      (node (ref "Cd193") (pin "1") (pinfunction "1_1") (pintype "passive"))
      (node (ref "Cd194") (pin "2") (pinfunction "2_2") (pintype "passive"))
      (node (ref "Cd201") (pin "1") (pinfunction "1_1") (pintype "passive"))
      (node (ref "Cd202") (pin "2") (pinfunction "2_2") (pintype "passive"))
      (node (ref "Cd203") (pin "1") (pinfunction "1_1") (pintype "passive"))
      (node (ref "Cd204") (pin "2") (pinfunction "2_2") (pintype "passive"))
      (node (ref "Cd21") (pin "1") (pinfunction "1_1") (pintype "passive"))
      (node (ref "Cd22") (pin "2") (pinfunction "2_2") (pintype "passive"))
      (node (ref "Cd23") (pin "1") (pinfunction "1_1") (pintype "passive"))
      (node (ref "Cd24") (pin "2") (pinfunction "2_2") (pintype "passive"))
      (node (ref "Cd31") (pin "1") (pinfunction "1_1") (pintype "passive"))
      (node (ref "Cd32") (pin "2") (pinfunction "2_2") (pintype "passive"))
      (node (ref "Cd33") (pin "1") (pinfunction "1_1") (pintype "passive"))
      (node (ref "Cd34") (pin "2") (pinfunction "2_2") (pintype "passive"))
      (node (ref "Cd41") (pin "1") (pinfunction "1_1") (pintype "passive"))
      (node (ref "Cd42") (pin "2") (pinfunction "2_2") (pintype "passive"))
      (node (ref "Cd43") (pin "1") (pinfunction "1_1") (pintype "passive"))
      (node (ref "Cd44") (pin "2") (pinfunction "2_2") (pintype "passive"))
      (node (ref "Cd51") (pin "1") (pinfunction "1_1") (pintype "passive"))
      (node (ref "Cd52") (pin "2") (pinfunction "2_2") (pintype "passive"))
      (node (ref "Cd53") (pin "1") (pinfunction "1_1") (pintype "passive"))
      (node (ref "Cd54") (pin "2") (pinfunction "2_2") (pintype "passive"))
      (node (ref "Cd61") (pin "1") (pinfunction "1_1") (pintype "passive"))
      (node (ref "Cd62") (pin "2") (pinfunction "2_2") (pintype "passive"))
      (node (ref "Cd63") (pin "1") (pinfunction "1_1") (pintype "passive"))
      (node (ref "Cd64") (pin "2") (pinfunction "2_2") (pintype "passive"))
      (node (ref "Cd71") (pin "1") (pinfunction "1_1") (pintype "passive"))
      (node (ref "Cd72") (pin "2") (pinfunction "2_2") (pintype "passive"))
      (node (ref "Cd73") (pin "1") (pinfunction "1_1") (pintype "passive"))
      (node (ref "Cd74") (pin "2") (pinfunction "2_2") (pintype "passive"))
      (node (ref "Cd81") (pin "1") (pinfunction "1_1") (pintype "passive"))
      (node (ref "Cd82") (pin "2") (pinfunction "2_2") (pintype "passive"))
      (node (ref "Cd83") (pin "1") (pinfunction "1_1") (pintype "passive"))
      (node (ref "Cd84") (pin "2") (pinfunction "2_2") (pintype "passive"))
      (node (ref "Cd91") (pin "1") (pinfunction "1_1") (pintype "passive"))
      (node (ref "Cd92") (pin "2") (pinfunction "2_2") (pintype "passive"))
      (node (ref "Cd93") (pin "1") (pinfunction "1_1") (pintype "passive"))
      (node (ref "Cd94") (pin "2") (pinfunction "2_2") (pintype "passive"))
      (node (ref "Ce1") (pin "1") (pinfunction "1_1") (pintype "passive"))
      (node (ref "Ce10") (pin "1") (pinfunction "1_1") (pintype "passive"))
      (node (ref "Ce11") (pin "1") (pinfunction "1_1") (pintype "passive"))
      (node (ref "Ce12") (pin "1") (pinfunction "1_1") (pintype "passive"))
      (node (ref "Ce13") (pin "1") (pinfunction "1_1") (pintype "passive"))
      (node (ref "Ce14") (pin "1") (pinfunction "1_1") (pintype "passive"))
      (node (ref "Ce15") (pin "1") (pinfunction "1_1") (pintype "passive"))
      (node (ref "Ce16") (pin "1") (pinfunction "1_1") (pintype "passive"))
      (node (ref "Ce17") (pin "1") (pinfunction "1_1") (pintype "passive"))
      (node (ref "Ce18") (pin "1") (pinfunction "1_1") (pintype "passive"))
      (node (ref "Ce19") (pin "1") (pinfunction "1_1") (pintype "passive"))
      (node (ref "Ce2") (pin "1") (pinfunction "1_1") (pintype "passive"))
      (node (ref "Ce20") (pin "1") (pinfunction "1_1") (pintype "passive"))
      (node (ref "Ce3") (pin "1") (pinfunction "1_1") (pintype "passive"))
      (node (ref "Ce4") (pin "1") (pinfunction "1_1") (pintype "passive"))
      (node (ref "Ce5") (pin "1") (pinfunction "1_1") (pintype "passive"))
      (node (ref "Ce6") (pin "1") (pinfunction "1_1") (pintype "passive"))
      (node (ref "Ce7") (pin "1") (pinfunction "1_1") (pintype "passive"))
      (node (ref "Ce8") (pin "1") (pinfunction "1_1") (pintype "passive"))
      (node (ref "Ce9") (pin "1") (pinfunction "1_1") (pintype "passive"))
      (node (ref "J1") (pin "2") (pinfunction "GND_2") (pintype "passive"))
      (node (ref "J1") (pin "3") (pinfunction "GND_3") (pintype "passive"))
      (node (ref "J1") (pin "4") (pinfunction "GND_4") (pintype "passive"))
      (node (ref "J1") (pin "5") (pinfunction "GND_5") (pintype "passive"))
      (node (ref "J10") (pin "2") (pinfunction "GND_2") (pintype "passive"))
      (node (ref "J10") (pin "3") (pinfunction "GND_3") (pintype "passive"))
      (node (ref "J10") (pin "4") (pinfunction "GND_4") (pintype "passive"))
      (node (ref "J10") (pin "5") (pinfunction "GND_5") (pintype "passive"))
      (node (ref "J12") (pin "2") (pinfunction "GND_2") (pintype "passive"))
      (node (ref "J12") (pin "3") (pinfunction "GND_3") (pintype "passive"))
      (node (ref "J12") (pin "4") (pinfunction "GND_4") (pintype "passive"))
      (node (ref "J12") (pin "5") (pinfunction "GND_5") (pintype "passive"))
      (node (ref "J19") (pin "2") (pinfunction "GND_2") (pintype "passive"))
      (node (ref "J19") (pin "3") (pinfunction "GND_3") (pintype "passive"))
      (node (ref "J19") (pin "4") (pinfunction "GND_4") (pintype "passive"))
      (node (ref "J19") (pin "5") (pinfunction "GND_5") (pintype "passive"))
      (node (ref "J3") (pin "2") (pinfunction "GND_2") (pintype "passive"))
      (node (ref "J3") (pin "3") (pinfunction "GND_3") (pintype "passive"))
      (node (ref "J3") (pin "4") (pinfunction "GND_4") (pintype "passive"))
      (node (ref "J3") (pin "5") (pinfunction "GND_5") (pintype "passive"))
      (node (ref "J8") (pin "2") (pinfunction "GND_2") (pintype "passive"))
      (node (ref "J8") (pin "3") (pinfunction "GND_3") (pintype "passive"))
      (node (ref "J8") (pin "4") (pinfunction "GND_4") (pintype "passive"))
      (node (ref "J8") (pin "5") (pinfunction "GND_5") (pintype "passive"))
      (node (ref "JIN") (pin "17") (pinfunction "GND1_17") (pintype "passive"))
      (node (ref "JIN") (pin "18") (pinfunction "GND2_18") (pintype "passive"))
      (node (ref "JIN") (pin "35") (pinfunction "35_35") (pintype "passive"))
      (node (ref "JIN") (pin "36") (pinfunction "36_36") (pintype "passive"))
      (node (ref "JIN") (pin "37") (pinfunction "37_37") (pintype "passive"))
      (node (ref "JIN") (pin "38") (pinfunction "38_38") (pintype "passive"))
      (node (ref "JIN") (pin "39") (pinfunction "39_39") (pintype "passive"))
      (node (ref "JIN") (pin "40") (pinfunction "40_40") (pintype "passive"))
      (node (ref "JIN") (pin "41") (pinfunction "41_41") (pintype "passive"))
      (node (ref "JIN") (pin "42") (pinfunction "42_42") (pintype "passive"))
      (node (ref "JIN") (pin "43") (pinfunction "43_43") (pintype "passive"))
      (node (ref "JIN") (pin "44") (pinfunction "44_44") (pintype "passive"))
      (node (ref "JIN") (pin "45") (pinfunction "45_45") (pintype "passive"))
      (node (ref "JIN") (pin "46") (pinfunction "46_46") (pintype "passive"))
      (node (ref "JIN") (pin "47") (pinfunction "47_47") (pintype "passive"))
      (node (ref "JIN") (pin "48") (pinfunction "48_48") (pintype "passive"))
      (node (ref "JIN") (pin "49") (pinfunction "49_49") (pintype "passive"))
      (node (ref "JIN") (pin "50") (pinfunction "50_50") (pintype "passive"))
      (node (ref "JIN") (pin "51") (pinfunction "51_51") (pintype "passive"))
      (node (ref "JIN") (pin "52") (pinfunction "52_52") (pintype "passive"))
      (node (ref "JIN") (pin "53") (pinfunction "53_53") (pintype "passive"))
      (node (ref "JIN") (pin "54") (pinfunction "54_54") (pintype "passive"))
      (node (ref "JIN") (pin "55") (pinfunction "55_55") (pintype "passive"))
      (node (ref "JIN") (pin "56") (pinfunction "56_56") (pintype "passive"))
      (node (ref "JIN") (pin "57") (pinfunction "57_57") (pintype "passive"))
      (node (ref "JIN") (pin "58") (pinfunction "58_58") (pintype "passive"))
      (node (ref "JIN") (pin "59") (pinfunction "59_59") (pintype "passive"))
      (node (ref "JIN") (pin "60") (pinfunction "60_60") (pintype "passive"))
      (node (ref "JIN") (pin "61") (pinfunction "61_61") (pintype "passive"))
      (node (ref "JIN") (pin "62") (pinfunction "62_62") (pintype "passive"))
      (node (ref "JIN") (pin "63") (pinfunction "63_63") (pintype "passive"))
      (node (ref "JIN") (pin "64") (pinfunction "64_64") (pintype "passive"))
      (node (ref "JIN") (pin "65") (pinfunction "65_65") (pintype "passive"))
      (node (ref "JIN") (pin "66") (pinfunction "66_66") (pintype "passive"))
      (node (ref "JIN") (pin "67") (pinfunction "67_67") (pintype "passive"))
      (node (ref "JIN") (pin "68") (pinfunction "68_68") (pintype "passive"))
      (node (ref "JIN") (pin "M1") (pinfunction "M1_M1") (pintype "passive"))
      (node (ref "JIN") (pin "M2") (pinfunction "M2_M2") (pintype "passive"))
      (node (ref "JOUT") (pin "19") (pinfunction "19_19") (pintype "passive"))
      (node (ref "JOUT") (pin "20") (pinfunction "20_20") (pintype "passive"))
      (node (ref "JOUT") (pin "6") (pinfunction "6_6") (pintype "passive"))
      (node (ref "JOUT") (pin "7") (pinfunction "7_7") (pintype "passive"))
      (node (ref "JOUT") (pin "8") (pinfunction "8_8") (pintype "passive"))
      (node (ref "JOUT") (pin "M1") (pinfunction "M1_M1") (pintype "passive"))
      (node (ref "JOUT") (pin "M2") (pinfunction "M2_M2") (pintype "passive"))
      (node (ref "Rg1") (pin "1") (pinfunction "1_1") (pintype "passive"))
      (node (ref "Rg10") (pin "1") (pinfunction "1_1") (pintype "passive"))
      (node (ref "Rg11") (pin "1") (pinfunction "1_1") (pintype "passive"))
      (node (ref "Rg12") (pin "1") (pinfunction "1_1") (pintype "passive"))
      (node (ref "Rg13") (pin "1") (pinfunction "1_1") (pintype "passive"))
      (node (ref "Rg14") (pin "1") (pinfunction "1_1") (pintype "passive"))
      (node (ref "Rg15") (pin "1") (pinfunction "1_1") (pintype "passive"))
      (node (ref "Rg16") (pin "1") (pinfunction "1_1") (pintype "passive"))
      (node (ref "Rg17") (pin "1") (pinfunction "1_1") (pintype "passive"))
      (node (ref "Rg18") (pin "1") (pinfunction "1_1") (pintype "passive"))
      (node (ref "Rg19") (pin "1") (pinfunction "1_1") (pintype "passive"))
      (node (ref "Rg2") (pin "1") (pinfunction "1_1") (pintype "passive"))
      (node (ref "Rg20") (pin "1") (pinfunction "1_1") (pintype "passive"))
      (node (ref "Rg3") (pin "1") (pinfunction "1_1") (pintype "passive"))
      (node (ref "Rg4") (pin "1") (pinfunction "1_1") (pintype "passive"))
      (node (ref "Rg5") (pin "1") (pinfunction "1_1") (pintype "passive"))
      (node (ref "Rg6") (pin "1") (pinfunction "1_1") (pintype "passive"))
      (node (ref "Rg7") (pin "1") (pinfunction "1_1") (pintype "passive"))
      (node (ref "Rg8") (pin "1") (pinfunction "1_1") (pintype "passive"))
      (node (ref "Rg9") (pin "1") (pinfunction "1_1") (pintype "passive"))
      (node (ref "T1") (pin "1") (pinfunction "1_1") (pintype "passive"))
      (node (ref "T1") (pin "10") (pinfunction "10_10") (pintype "passive"))
      (node (ref "T1") (pin "11") (pinfunction "11_11") (pintype "passive"))
      (node (ref "T1") (pin "13") (pinfunction "13_13") (pintype "passive"))
      (node (ref "T1") (pin "14") (pinfunction "14_14") (pintype "passive"))
      (node (ref "T1") (pin "15") (pinfunction "15_15") (pintype "passive"))
      (node (ref "T1") (pin "16") (pinfunction "16_16") (pintype "passive"))
      (node (ref "T1") (pin "2") (pinfunction "2_2") (pintype "passive"))
      (node (ref "T1") (pin "4") (pinfunction "4_4") (pintype "passive"))
      (node (ref "T1") (pin "5") (pinfunction "5_5") (pintype "passive"))
      (node (ref "T1") (pin "6") (pinfunction "6_6") (pintype "passive"))
      (node (ref "T1") (pin "7") (pinfunction "7_7") (pintype "passive"))
      (node (ref "T1") (pin "8") (pinfunction "8_8") (pintype "passive"))
      (node (ref "T10") (pin "1") (pinfunction "1_1") (pintype "passive"))
      (node (ref "T10") (pin "10") (pinfunction "10_10") (pintype "passive"))
      (node (ref "T10") (pin "11") (pinfunction "11_11") (pintype "passive"))
      (node (ref "T10") (pin "13") (pinfunction "13_13") (pintype "passive"))
      (node (ref "T10") (pin "14") (pinfunction "14_14") (pintype "passive"))
      (node (ref "T10") (pin "15") (pinfunction "15_15") (pintype "passive"))
      (node (ref "T10") (pin "16") (pinfunction "16_16") (pintype "passive"))
      (node (ref "T10") (pin "2") (pinfunction "2_2") (pintype "passive"))
      (node (ref "T10") (pin "4") (pinfunction "4_4") (pintype "passive"))
      (node (ref "T10") (pin "5") (pinfunction "5_5") (pintype "passive"))
      (node (ref "T10") (pin "6") (pinfunction "6_6") (pintype "passive"))
      (node (ref "T10") (pin "7") (pinfunction "7_7") (pintype "passive"))
      (node (ref "T10") (pin "8") (pinfunction "8_8") (pintype "passive"))
      (node (ref "T12") (pin "1") (pinfunction "1_1") (pintype "passive"))
      (node (ref "T12") (pin "10") (pinfunction "10_10") (pintype "passive"))
      (node (ref "T12") (pin "11") (pinfunction "11_11") (pintype "passive"))
      (node (ref "T12") (pin "13") (pinfunction "13_13") (pintype "passive"))
      (node (ref "T12") (pin "14") (pinfunction "14_14") (pintype "passive"))
      (node (ref "T12") (pin "15") (pinfunction "15_15") (pintype "passive"))
      (node (ref "T12") (pin "16") (pinfunction "16_16") (pintype "passive"))
      (node (ref "T12") (pin "2") (pinfunction "2_2") (pintype "passive"))
      (node (ref "T12") (pin "4") (pinfunction "4_4") (pintype "passive"))
      (node (ref "T12") (pin "5") (pinfunction "5_5") (pintype "passive"))
      (node (ref "T12") (pin "6") (pinfunction "6_6") (pintype "passive"))
      (node (ref "T12") (pin "7") (pinfunction "7_7") (pintype "passive"))
      (node (ref "T12") (pin "8") (pinfunction "8_8") (pintype "passive"))
      (node (ref "T19") (pin "1") (pinfunction "1_1") (pintype "passive"))
      (node (ref "T19") (pin "10") (pinfunction "10_10") (pintype "passive"))
      (node (ref "T19") (pin "11") (pinfunction "11_11") (pintype "passive"))
      (node (ref "T19") (pin "13") (pinfunction "13_13") (pintype "passive"))
      (node (ref "T19") (pin "14") (pinfunction "14_14") (pintype "passive"))
      (node (ref "T19") (pin "15") (pinfunction "15_15") (pintype "passive"))
      (node (ref "T19") (pin "16") (pinfunction "16_16") (pintype "passive"))
      (node (ref "T19") (pin "2") (pinfunction "2_2") (pintype "passive"))
      (node (ref "T19") (pin "4") (pinfunction "4_4") (pintype "passive"))
      (node (ref "T19") (pin "5") (pinfunction "5_5") (pintype "passive"))
      (node (ref "T19") (pin "6") (pinfunction "6_6") (pintype "passive"))
      (node (ref "T19") (pin "7") (pinfunction "7_7") (pintype "passive"))
      (node (ref "T19") (pin "8") (pinfunction "8_8") (pintype "passive"))
      (node (ref "T3") (pin "1") (pinfunction "1_1") (pintype "passive"))
      (node (ref "T3") (pin "10") (pinfunction "10_10") (pintype "passive"))
      (node (ref "T3") (pin "11") (pinfunction "11_11") (pintype "passive"))
      (node (ref "T3") (pin "13") (pinfunction "13_13") (pintype "passive"))
      (node (ref "T3") (pin "14") (pinfunction "14_14") (pintype "passive"))
      (node (ref "T3") (pin "15") (pinfunction "15_15") (pintype "passive"))
      (node (ref "T3") (pin "16") (pinfunction "16_16") (pintype "passive"))
      (node (ref "T3") (pin "2") (pinfunction "2_2") (pintype "passive"))
      (node (ref "T3") (pin "4") (pinfunction "4_4") (pintype "passive"))
      (node (ref "T3") (pin "5") (pinfunction "5_5") (pintype "passive"))
      (node (ref "T3") (pin "6") (pinfunction "6_6") (pintype "passive"))
      (node (ref "T3") (pin "7") (pinfunction "7_7") (pintype "passive"))
      (node (ref "T3") (pin "8") (pinfunction "8_8") (pintype "passive"))
      (node (ref "T8") (pin "1") (pinfunction "1_1") (pintype "passive"))
      (node (ref "T8") (pin "10") (pinfunction "10_10") (pintype "passive"))
      (node (ref "T8") (pin "11") (pinfunction "11_11") (pintype "passive"))
      (node (ref "T8") (pin "13") (pinfunction "13_13") (pintype "passive"))
      (node (ref "T8") (pin "14") (pinfunction "14_14") (pintype "passive"))
      (node (ref "T8") (pin "15") (pinfunction "15_15") (pintype "passive"))
      (node (ref "T8") (pin "16") (pinfunction "16_16") (pintype "passive"))
      (node (ref "T8") (pin "2") (pinfunction "2_2") (pintype "passive"))
      (node (ref "T8") (pin "4") (pinfunction "4_4") (pintype "passive"))
      (node (ref "T8") (pin "5") (pinfunction "5_5") (pintype "passive"))
      (node (ref "T8") (pin "6") (pinfunction "6_6") (pintype "passive"))
      (node (ref "T8") (pin "7") (pinfunction "7_7") (pintype "passive"))
      (node (ref "T8") (pin "8") (pinfunction "8_8") (pintype "passive"))
      (node (ref "U1") (pin "1") (pinfunction "E/D_COM_1") (pintype "power_in"))
      (node (ref "U1") (pin "9") (pinfunction "EP_9") (pintype "power_in"))
      (node (ref "U10") (pin "1") (pinfunction "E/D_COM_1") (pintype "power_in"))
      (node (ref "U10") (pin "9") (pinfunction "EP_9") (pintype "power_in"))
      (node (ref "U11") (pin "1") (pinfunction "E/D_COM_1") (pintype "power_in"))
      (node (ref "U11") (pin "9") (pinfunction "EP_9") (pintype "power_in"))
      (node (ref "U12") (pin "1") (pinfunction "E/D_COM_1") (pintype "power_in"))
      (node (ref "U12") (pin "9") (pinfunction "EP_9") (pintype "power_in"))
      (node (ref "U13") (pin "1") (pinfunction "E/D_COM_1") (pintype "power_in"))
      (node (ref "U13") (pin "9") (pinfunction "EP_9") (pintype "power_in"))
      (node (ref "U14") (pin "1") (pinfunction "E/D_COM_1") (pintype "power_in"))
      (node (ref "U14") (pin "9") (pinfunction "EP_9") (pintype "power_in"))
      (node (ref "U15") (pin "1") (pinfunction "E/D_COM_1") (pintype "power_in"))
      (node (ref "U15") (pin "9") (pinfunction "EP_9") (pintype "power_in"))
      (node (ref "U16") (pin "1") (pinfunction "E/D_COM_1") (pintype "power_in"))
      (node (ref "U16") (pin "9") (pinfunction "EP_9") (pintype "power_in"))
      (node (ref "U17") (pin "1") (pinfunction "E/D_COM_1") (pintype "power_in"))
      (node (ref "U17") (pin "9") (pinfunction "EP_9") (pintype "power_in"))
      (node (ref "U18") (pin "1") (pinfunction "E/D_COM_1") (pintype "power_in"))
      (node (ref "U18") (pin "9") (pinfunction "EP_9") (pintype "power_in"))
      (node (ref "U19") (pin "1") (pinfunction "E/D_COM_1") (pintype "power_in"))
      (node (ref "U19") (pin "9") (pinfunction "EP_9") (pintype "power_in"))
      (node (ref "U2") (pin "1") (pinfunction "E/D_COM_1") (pintype "power_in"))
      (node (ref "U2") (pin "9") (pinfunction "EP_9") (pintype "power_in"))
      (node (ref "U20") (pin "1") (pinfunction "E/D_COM_1") (pintype "power_in"))
      (node (ref "U20") (pin "9") (pinfunction "EP_9") (pintype "power_in"))
      (node (ref "U3") (pin "1") (pinfunction "E/D_COM_1") (pintype "power_in"))
      (node (ref "U3") (pin "9") (pinfunction "EP_9") (pintype "power_in"))
      (node (ref "U4") (pin "1") (pinfunction "E/D_COM_1") (pintype "power_in"))
      (node (ref "U4") (pin "9") (pinfunction "EP_9") (pintype "power_in"))
      (node (ref "U5") (pin "1") (pinfunction "E/D_COM_1") (pintype "power_in"))
      (node (ref "U5") (pin "9") (pinfunction "EP_9") (pintype "power_in"))
      (node (ref "U6") (pin "1") (pinfunction "E/D_COM_1") (pintype "power_in"))
      (node (ref "U6") (pin "9") (pinfunction "EP_9") (pintype "power_in"))
      (node (ref "U7") (pin "1") (pinfunction "E/D_COM_1") (pintype "power_in"))
      (node (ref "U7") (pin "9") (pinfunction "EP_9") (pintype "power_in"))
      (node (ref "U8") (pin "1") (pinfunction "E/D_COM_1") (pintype "power_in"))
      (node (ref "U8") (pin "9") (pinfunction "EP_9") (pintype "power_in"))
      (node (ref "U9") (pin "1") (pinfunction "E/D_COM_1") (pintype "power_in"))
      (node (ref "U9") (pin "9") (pinfunction "EP_9") (pintype "power_in"))
    )
    (net (code "71") (name "Net-(T1-RF)") (class "Default")
      (node (ref "J1") (pin "1") (pinfunction "1_1") (pintype "passive"))
      (node (ref "T1") (pin "9") (pinfunction "RF_9") (pintype "input"))
    )
    (net (code "72") (name "Net-(T3-RF)") (class "Default")
      (node (ref "J3") (pin "1") (pinfunction "1_1") (pintype "passive"))
      (node (ref "T3") (pin "9") (pinfunction "RF_9") (pintype "input"))
    )
    (net (code "73") (name "Net-(T8-RF)") (class "Default")
      (node (ref "J8") (pin "1") (pinfunction "1_1") (pintype "passive"))
      (node (ref "T8") (pin "9") (pinfunction "RF_9") (pintype "input"))
    )
    (net (code "74") (name "Net-(T10-RF)") (class "Default")
      (node (ref "J10") (pin "1") (pinfunction "1_1") (pintype "passive"))
      (node (ref "T10") (pin "9") (pinfunction "RF_9") (pintype "input"))
    )
    (net (code "75") (name "Net-(T12-RF)") (class "Default")
      (node (ref "J12") (pin "1") (pinfunction "1_1") (pintype "passive"))
      (node (ref "T12") (pin "9") (pinfunction "RF_9") (pintype "input"))
    )
    (net (code "76") (name "Net-(T19-RF)") (class "Default")
      (node (ref "J19") (pin "1") (pinfunction "1_1") (pintype "passive"))
      (node (ref "T19") (pin "9") (pinfunction "RF_9") (pintype "input"))
    )
    (net (code "77") (name "Net-(U1-IN-)") (class "Default")
      (node (ref "Rf1") (pin "1") (pinfunction "1_1") (pintype "passive"))
      (node (ref "Rg1") (pin "2") (pinfunction "2_2") (pintype "passive"))
      (node (ref "U1") (pin "2") (pinfunction "IN-_2") (pintype "input"))
    )
    (net (code "78") (name "Net-(U1-STATUS_FLAG)") (class "Default")
      (node (ref "Re1") (pin "1") (pinfunction "1_1") (pintype "passive"))
      (node (ref "U1") (pin "5") (pinfunction "STATUS_FLAG_5") (pintype "open_collector"))
    )
    (net (code "79") (name "Net-(U2-IN-)") (class "Default")
      (node (ref "Rf2") (pin "1") (pinfunction "1_1") (pintype "passive"))
      (node (ref "Rg2") (pin "2") (pinfunction "2_2") (pintype "passive"))
      (node (ref "U2") (pin "2") (pinfunction "IN-_2") (pintype "input"))
    )
    (net (code "80") (name "Net-(U2-STATUS_FLAG)") (class "Default")
      (node (ref "Re2") (pin "1") (pinfunction "1_1") (pintype "passive"))
      (node (ref "U2") (pin "5") (pinfunction "STATUS_FLAG_5") (pintype "open_collector"))
    )
    (net (code "81") (name "Net-(U3-IN-)") (class "Default")
      (node (ref "Rf3") (pin "1") (pinfunction "1_1") (pintype "passive"))
      (node (ref "Rg3") (pin "2") (pinfunction "2_2") (pintype "passive"))
      (node (ref "U3") (pin "2") (pinfunction "IN-_2") (pintype "input"))
    )
    (net (code "82") (name "Net-(U3-STATUS_FLAG)") (class "Default")
      (node (ref "Re3") (pin "1") (pinfunction "1_1") (pintype "passive"))
      (node (ref "U3") (pin "5") (pinfunction "STATUS_FLAG_5") (pintype "open_collector"))
    )
    (net (code "83") (name "Net-(U4-IN-)") (class "Default")
      (node (ref "Rf4") (pin "1") (pinfunction "1_1") (pintype "passive"))
      (node (ref "Rg4") (pin "2") (pinfunction "2_2") (pintype "passive"))
      (node (ref "U4") (pin "2") (pinfunction "IN-_2") (pintype "input"))
    )
    (net (code "84") (name "Net-(U4-STATUS_FLAG)") (class "Default")
      (node (ref "Re4") (pin "1") (pinfunction "1_1") (pintype "passive"))
      (node (ref "U4") (pin "5") (pinfunction "STATUS_FLAG_5") (pintype "open_collector"))
    )
    (net (code "85") (name "Net-(U5-IN-)") (class "Default")
      (node (ref "Rf5") (pin "1") (pinfunction "1_1") (pintype "passive"))
      (node (ref "Rg5") (pin "2") (pinfunction "2_2") (pintype "passive"))
      (node (ref "U5") (pin "2") (pinfunction "IN-_2") (pintype "input"))
    )
    (net (code "86") (name "Net-(U5-STATUS_FLAG)") (class "Default")
      (node (ref "Re5") (pin "1") (pinfunction "1_1") (pintype "passive"))
      (node (ref "U5") (pin "5") (pinfunction "STATUS_FLAG_5") (pintype "open_collector"))
    )
    (net (code "87") (name "Net-(U6-IN-)") (class "Default")
      (node (ref "Rf6") (pin "1") (pinfunction "1_1") (pintype "passive"))
      (node (ref "Rg6") (pin "2") (pinfunction "2_2") (pintype "passive"))
      (node (ref "U6") (pin "2") (pinfunction "IN-_2") (pintype "input"))
    )
    (net (code "88") (name "Net-(U6-STATUS_FLAG)") (class "Default")
      (node (ref "Re6") (pin "1") (pinfunction "1_1") (pintype "passive"))
      (node (ref "U6") (pin "5") (pinfunction "STATUS_FLAG_5") (pintype "open_collector"))
    )
    (net (code "89") (name "Net-(U7-IN-)") (class "Default")
      (node (ref "Rf7") (pin "1") (pinfunction "1_1") (pintype "passive"))
      (node (ref "Rg7") (pin "2") (pinfunction "2_2") (pintype "passive"))
      (node (ref "U7") (pin "2") (pinfunction "IN-_2") (pintype "input"))
    )
    (net (code "90") (name "Net-(U7-STATUS_FLAG)") (class "Default")
      (node (ref "Re7") (pin "1") (pinfunction "1_1") (pintype "passive"))
      (node (ref "U7") (pin "5") (pinfunction "STATUS_FLAG_5") (pintype "open_collector"))
    )
    (net (code "91") (name "Net-(U8-IN-)") (class "Default")
      (node (ref "Rf8") (pin "1") (pinfunction "1_1") (pintype "passive"))
      (node (ref "Rg8") (pin "2") (pinfunction "2_2") (pintype "passive"))
      (node (ref "U8") (pin "2") (pinfunction "IN-_2") (pintype "input"))
    )
    (net (code "92") (name "Net-(U8-STATUS_FLAG)") (class "Default")
      (node (ref "Re8") (pin "1") (pinfunction "1_1") (pintype "passive"))
      (node (ref "U8") (pin "5") (pinfunction "STATUS_FLAG_5") (pintype "open_collector"))
    )
    (net (code "93") (name "Net-(U9-IN-)") (class "Default")
      (node (ref "Rf9") (pin "1") (pinfunction "1_1") (pintype "passive"))
      (node (ref "Rg9") (pin "2") (pinfunction "2_2") (pintype "passive"))
      (node (ref "U9") (pin "2") (pinfunction "IN-_2") (pintype "input"))
    )
    (net (code "94") (name "Net-(U9-STATUS_FLAG)") (class "Default")
      (node (ref "Re9") (pin "1") (pinfunction "1_1") (pintype "passive"))
      (node (ref "U9") (pin "5") (pinfunction "STATUS_FLAG_5") (pintype "open_collector"))
    )
    (net (code "95") (name "Net-(U10-IN-)") (class "Default")
      (node (ref "Rf10") (pin "1") (pinfunction "1_1") (pintype "passive"))
      (node (ref "Rg10") (pin "2") (pinfunction "2_2") (pintype "passive"))
      (node (ref "U10") (pin "2") (pinfunction "IN-_2") (pintype "input"))
    )
    (net (code "96") (name "Net-(U10-STATUS_FLAG)") (class "Default")
      (node (ref "Re10") (pin "1") (pinfunction "1_1") (pintype "passive"))
      (node (ref "U10") (pin "5") (pinfunction "STATUS_FLAG_5") (pintype "open_collector"))
    )
    (net (code "97") (name "Net-(U11-IN-)") (class "Default")
      (node (ref "Rf11") (pin "1") (pinfunction "1_1") (pintype "passive"))
      (node (ref "Rg11") (pin "2") (pinfunction "2_2") (pintype "passive"))
      (node (ref "U11") (pin "2") (pinfunction "IN-_2") (pintype "input"))
    )
    (net (code "98") (name "Net-(U11-STATUS_FLAG)") (class "Default")
      (node (ref "Re11") (pin "1") (pinfunction "1_1") (pintype "passive"))
      (node (ref "U11") (pin "5") (pinfunction "STATUS_FLAG_5") (pintype "open_collector"))
    )
    (net (code "99") (name "Net-(U12-IN-)") (class "Default")
      (node (ref "Rf12") (pin "1") (pinfunction "1_1") (pintype "passive"))
      (node (ref "Rg12") (pin "2") (pinfunction "2_2") (pintype "passive"))
      (node (ref "U12") (pin "2") (pinfunction "IN-_2") (pintype "input"))
    )
    (net (code "100") (name "Net-(U12-STATUS_FLAG)") (class "Default")
      (node (ref "Re12") (pin "1") (pinfunction "1_1") (pintype "passive"))
      (node (ref "U12") (pin "5") (pinfunction "STATUS_FLAG_5") (pintype "open_collector"))
    )
    (net (code "101") (name "Net-(U13-IN-)") (class "Default")
      (node (ref "Rf13") (pin "1") (pinfunction "1_1") (pintype "passive"))
      (node (ref "Rg13") (pin "2") (pinfunction "2_2") (pintype "passive"))
      (node (ref "U13") (pin "2") (pinfunction "IN-_2") (pintype "input"))
    )
    (net (code "102") (name "Net-(U13-STATUS_FLAG)") (class "Default")
      (node (ref "Re13") (pin "1") (pinfunction "1_1") (pintype "passive"))
      (node (ref "U13") (pin "5") (pinfunction "STATUS_FLAG_5") (pintype "open_collector"))
    )
    (net (code "103") (name "Net-(U14-IN-)") (class "Default")
      (node (ref "Rf14") (pin "1") (pinfunction "1_1") (pintype "passive"))
      (node (ref "Rg14") (pin "2") (pinfunction "2_2") (pintype "passive"))
      (node (ref "U14") (pin "2") (pinfunction "IN-_2") (pintype "input"))
    )
    (net (code "104") (name "Net-(U14-STATUS_FLAG)") (class "Default")
      (node (ref "Re14") (pin "1") (pinfunction "1_1") (pintype "passive"))
      (node (ref "U14") (pin "5") (pinfunction "STATUS_FLAG_5") (pintype "open_collector"))
    )
    (net (code "105") (name "Net-(U15-IN-)") (class "Default")
      (node (ref "Rf15") (pin "1") (pinfunction "1_1") (pintype "passive"))
      (node (ref "Rg15") (pin "2") (pinfunction "2_2") (pintype "passive"))
      (node (ref "U15") (pin "2") (pinfunction "IN-_2") (pintype "input"))
    )
    (net (code "106") (name "Net-(U15-STATUS_FLAG)") (class "Default")
      (node (ref "Re15") (pin "1") (pinfunction "1_1") (pintype "passive"))
      (node (ref "U15") (pin "5") (pinfunction "STATUS_FLAG_5") (pintype "open_collector"))
    )
    (net (code "107") (name "Net-(U16-IN-)") (class "Default")
      (node (ref "Rf16") (pin "1") (pinfunction "1_1") (pintype "passive"))
      (node (ref "Rg16") (pin "2") (pinfunction "2_2") (pintype "passive"))
      (node (ref "U16") (pin "2") (pinfunction "IN-_2") (pintype "input"))
    )
    (net (code "108") (name "Net-(U16-STATUS_FLAG)") (class "Default")
      (node (ref "Re16") (pin "1") (pinfunction "1_1") (pintype "passive"))
      (node (ref "U16") (pin "5") (pinfunction "STATUS_FLAG_5") (pintype "open_collector"))
    )
    (net (code "109") (name "Net-(U17-IN-)") (class "Default")
      (node (ref "Rf17") (pin "1") (pinfunction "1_1") (pintype "passive"))
      (node (ref "Rg17") (pin "2") (pinfunction "2_2") (pintype "passive"))
      (node (ref "U17") (pin "2") (pinfunction "IN-_2") (pintype "input"))
    )
    (net (code "110") (name "Net-(U17-STATUS_FLAG)") (class "Default")
      (node (ref "Re17") (pin "1") (pinfunction "1_1") (pintype "passive"))
      (node (ref "U17") (pin "5") (pinfunction "STATUS_FLAG_5") (pintype "open_collector"))
    )
    (net (code "111") (name "Net-(U18-IN-)") (class "Default")
      (node (ref "Rf18") (pin "1") (pinfunction "1_1") (pintype "passive"))
      (node (ref "Rg18") (pin "2") (pinfunction "2_2") (pintype "passive"))
      (node (ref "U18") (pin "2") (pinfunction "IN-_2") (pintype "input"))
    )
    (net (code "112") (name "Net-(U18-STATUS_FLAG)") (class "Default")
      (node (ref "Re18") (pin "1") (pinfunction "1_1") (pintype "passive"))
      (node (ref "U18") (pin "5") (pinfunction "STATUS_FLAG_5") (pintype "open_collector"))
    )
    (net (code "113") (name "Net-(U19-IN-)") (class "Default")
      (node (ref "Rf19") (pin "1") (pinfunction "1_1") (pintype "passive"))
      (node (ref "Rg19") (pin "2") (pinfunction "2_2") (pintype "passive"))
      (node (ref "U19") (pin "2") (pinfunction "IN-_2") (pintype "input"))
    )
    (net (code "114") (name "Net-(U19-STATUS_FLAG)") (class "Default")
      (node (ref "Re19") (pin "1") (pinfunction "1_1") (pintype "passive"))
      (node (ref "U19") (pin "5") (pinfunction "STATUS_FLAG_5") (pintype "open_collector"))
    )
    (net (code "115") (name "Net-(U20-IN-)") (class "Default")
      (node (ref "Rf20") (pin "1") (pinfunction "1_1") (pintype "passive"))
      (node (ref "Rg20") (pin "2") (pinfunction "2_2") (pintype "passive"))
      (node (ref "U20") (pin "2") (pinfunction "IN-_2") (pintype "input"))
    )
    (net (code "116") (name "Net-(U20-STATUS_FLAG)") (class "Default")
      (node (ref "Re20") (pin "1") (pinfunction "1_1") (pintype "passive"))
      (node (ref "U20") (pin "5") (pinfunction "STATUS_FLAG_5") (pintype "open_collector"))
    )
    (net (code "117") (name "unconnected-(JIN-Z20-Pad23)") (class "Default")
      (node (ref "JIN") (pin "23") (pinfunction "Z20_23") (pintype "passive"))
    )
    (net (code "118") (name "unconnected-(JIN-Z21-Pad24)") (class "Default")
      (node (ref "JIN") (pin "24") (pinfunction "Z21_24") (pintype "passive"))
    )
    (net (code "119") (name "unconnected-(JIN-Z22-Pad25)") (class "Default")
      (node (ref "JIN") (pin "25") (pinfunction "Z22_25") (pintype "passive"))
    )
    (net (code "120") (name "unconnected-(JIN-Z23-Pad26)") (class "Default")
      (node (ref "JIN") (pin "26") (pinfunction "Z23_26") (pintype "passive"))
    )
    (net (code "121") (name "unconnected-(JIN-Z24-Pad27)") (class "Default")
      (node (ref "JIN") (pin "27") (pinfunction "Z24_27") (pintype "passive"))
    )
    (net (code "122") (name "unconnected-(JIN-Z25-Pad28)") (class "Default")
      (node (ref "JIN") (pin "28") (pinfunction "Z25_28") (pintype "passive"))
    )
    (net (code "123") (name "unconnected-(JIN-Z26-Pad29)") (class "Default")
      (node (ref "JIN") (pin "29") (pinfunction "Z26_29") (pintype "passive"))
    )
    (net (code "124") (name "unconnected-(JIN-Z27-Pad30)") (class "Default")
      (node (ref "JIN") (pin "30") (pinfunction "Z27_30") (pintype "passive"))
    )
    (net (code "125") (name "unconnected-(JIN-Z28-Pad31)") (class "Default")
      (node (ref "JIN") (pin "31") (pinfunction "Z28_31") (pintype "passive"))
    )
    (net (code "126") (name "unconnected-(JIN-Z29-Pad32)") (class "Default")
      (node (ref "JIN") (pin "32") (pinfunction "Z29_32") (pintype "passive"))
    )
    (net (code "127") (name "unconnected-(JIN-Z30-Pad33)") (class "Default")
      (node (ref "JIN") (pin "33") (pinfunction "Z30_33") (pintype "passive"))
    )
    (net (code "128") (name "unconnected-(JIN-Z31-Pad34)") (class "Default")
      (node (ref "JIN") (pin "34") (pinfunction "Z31_34") (pintype "passive"))
    )
  )
)
